# LEDSubMatrixHighDensity_v3.net
KiCad netlist of a schematic drawn in EAGLE
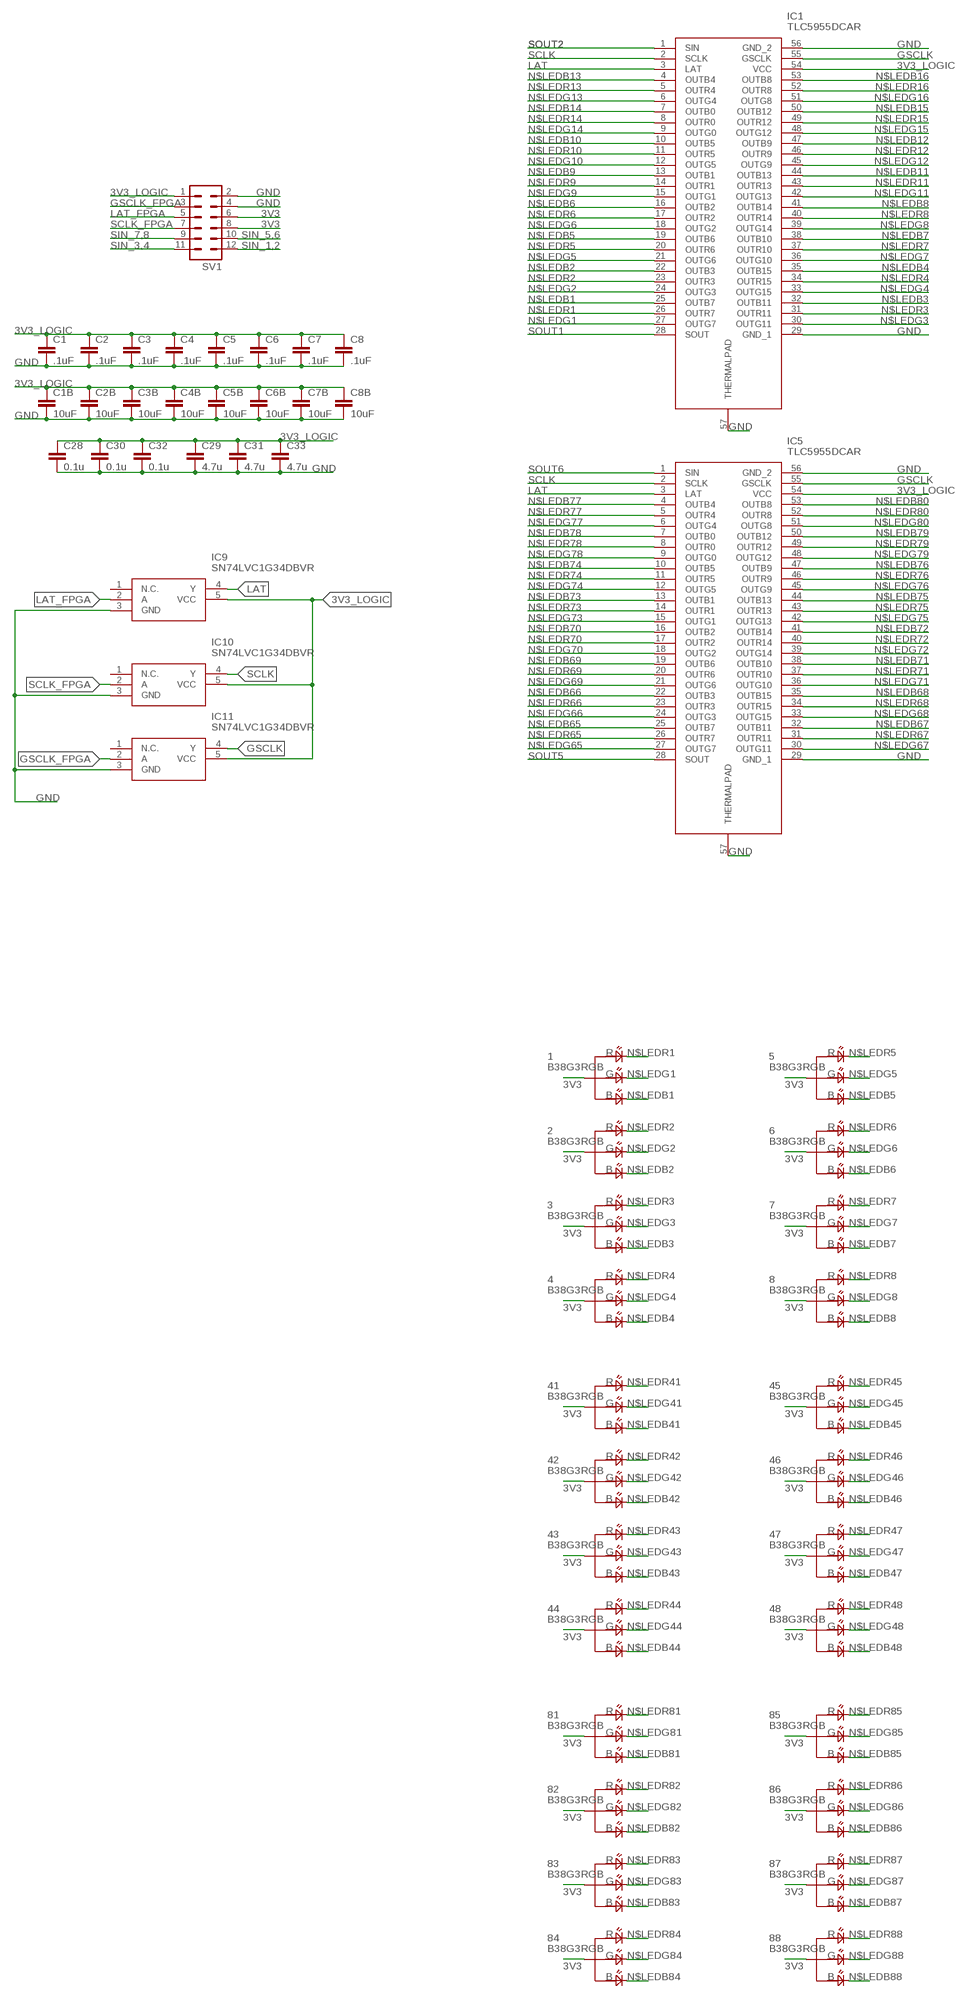
[diagram p0: schematic, sheet 1, part 1 of 2]
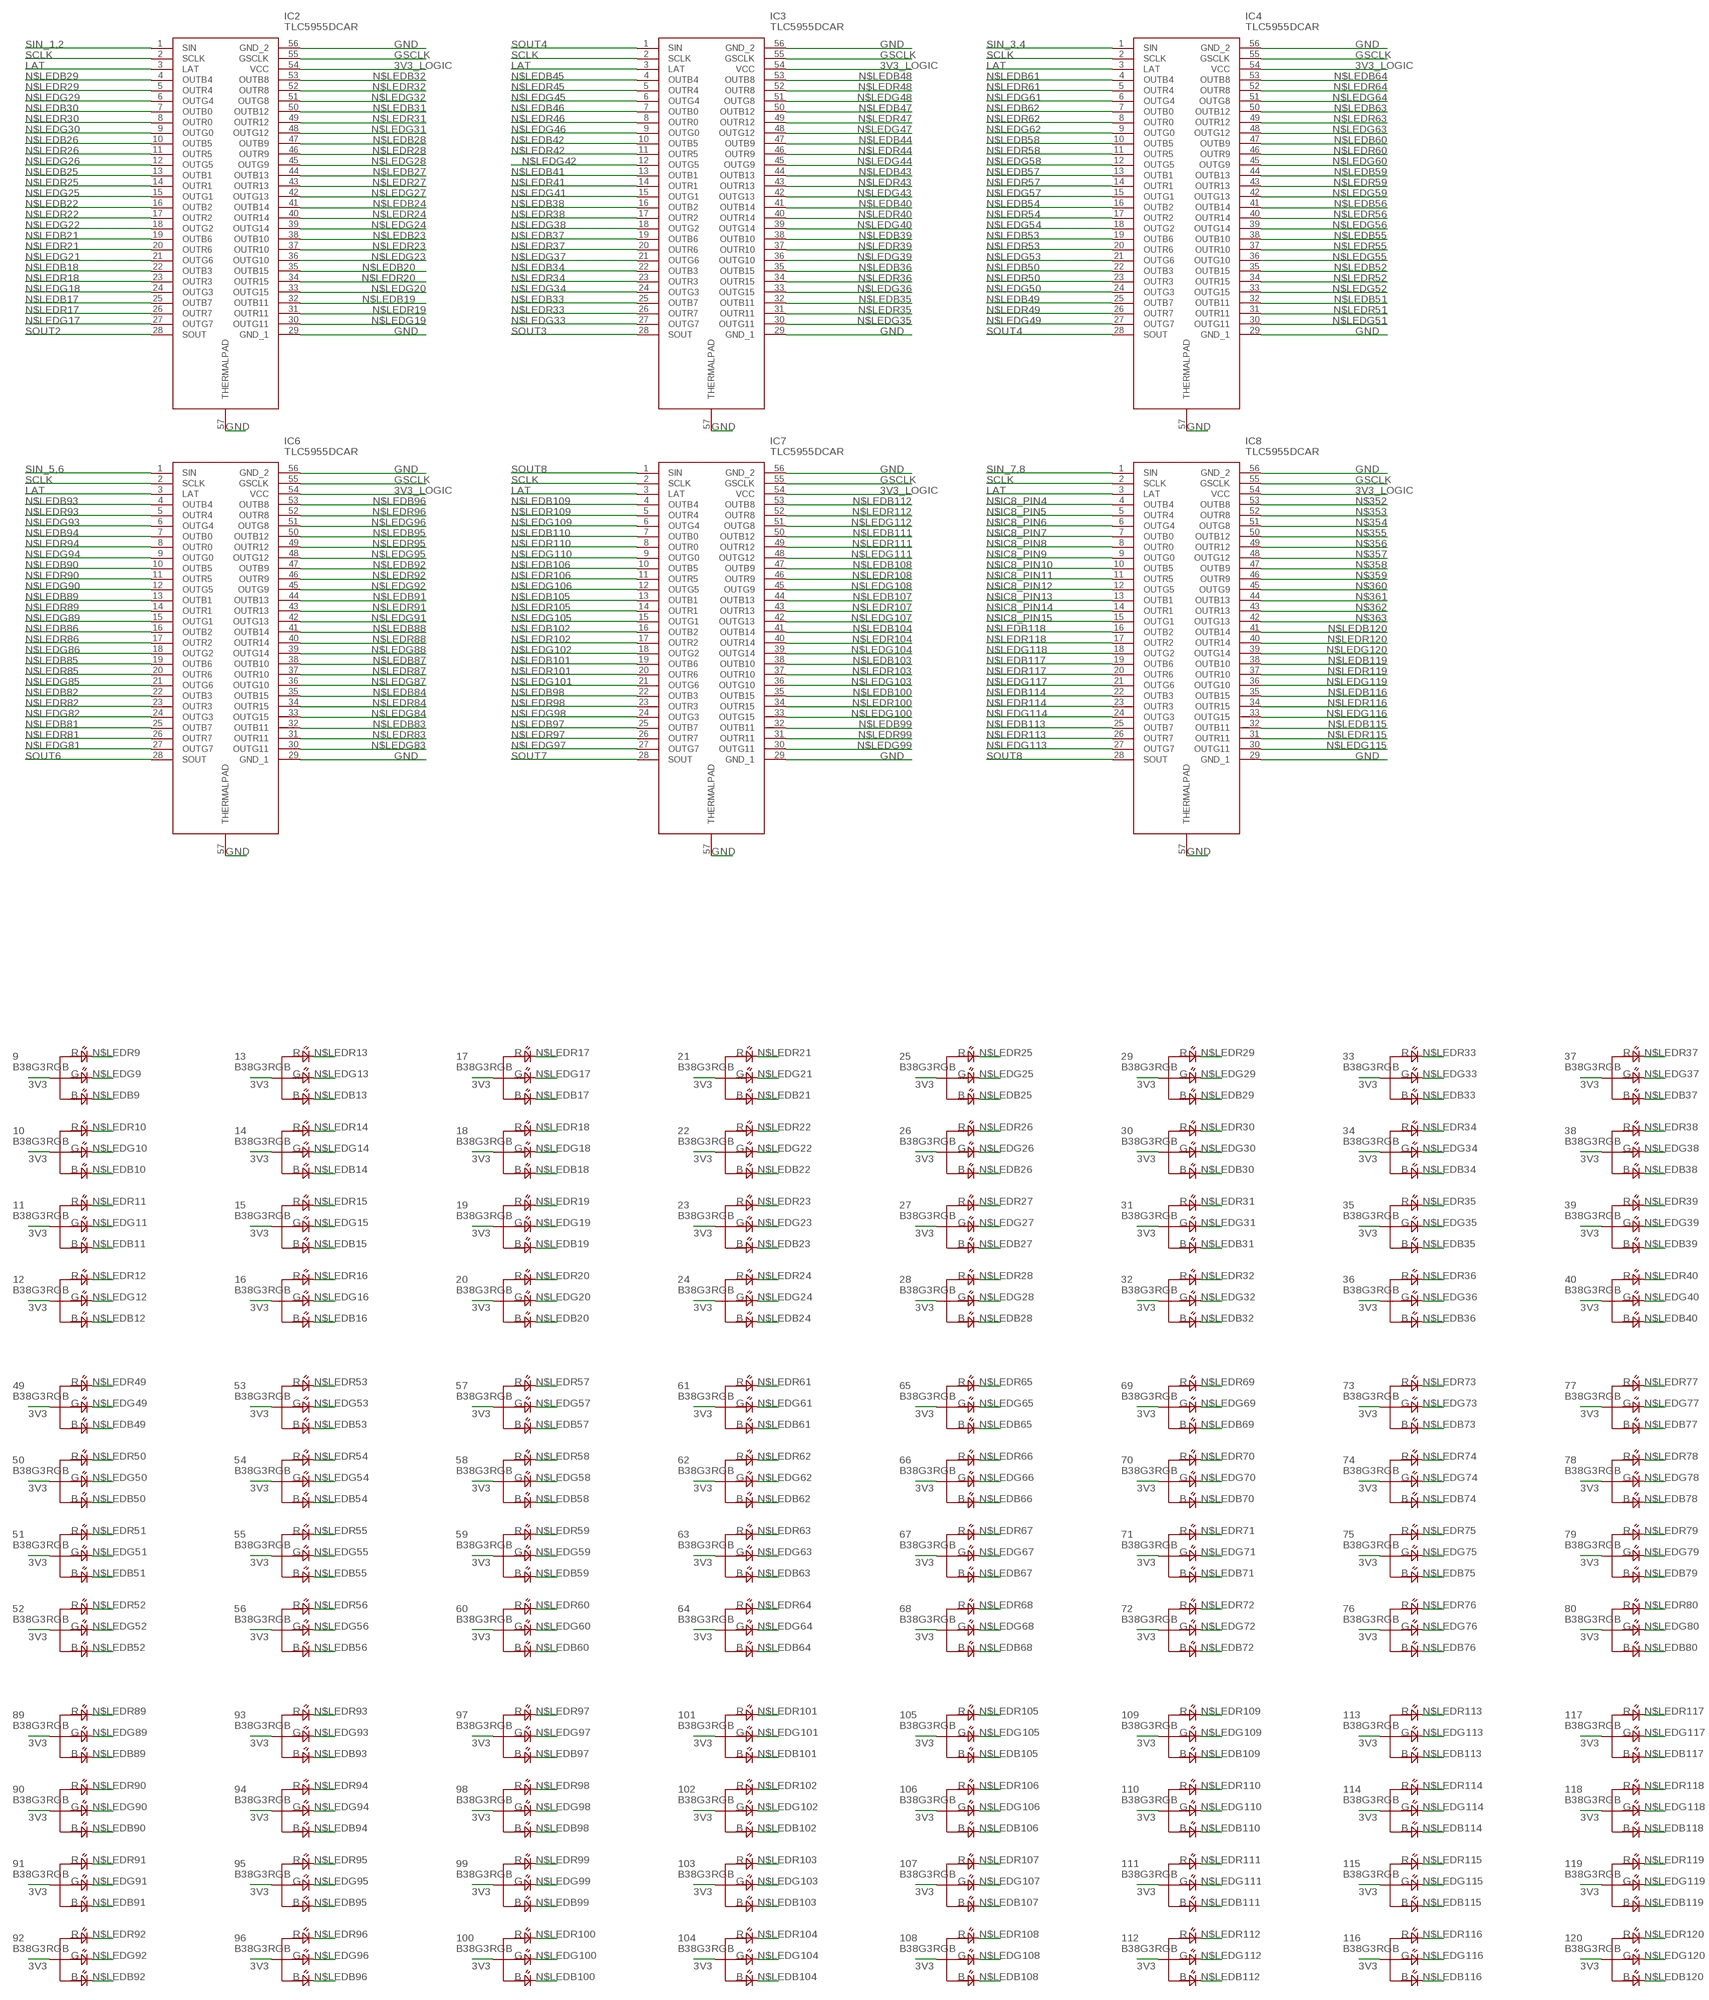
[diagram p1: schematic, sheet 1, part 2 of 2]

(export (version "E")
  (design (tool "Eeschema 10.0.6"))
  (components
    (comp (ref "1")
      (value "B38G3RGB")
      (footprint "eagle-import:B38G3RGB")
      (fields
        (field (name "ARROW_PART_NUMBER") "SML-LX0606IGC-TR")
        (field (name "MOUSER_PART_NUMBER") "696-SML-0606IGCTR")
      )
      (libsource (lib "eagle-import") (part "B38G3RGB"))
    )
    (comp (ref "2")
      (value "B38G3RGB")
      (footprint "eagle-import:B38G3RGB")
      (fields
        (field (name "ARROW_PART_NUMBER") "SML-LX0606IGC-TR")
        (field (name "MOUSER_PART_NUMBER") "696-SML-0606IGCTR")
      )
      (libsource (lib "eagle-import") (part "B38G3RGB"))
    )
    (comp (ref "3")
      (value "B38G3RGB")
      (footprint "eagle-import:B38G3RGB")
      (fields
        (field (name "ARROW_PART_NUMBER") "SML-LX0606IGC-TR")
        (field (name "MOUSER_PART_NUMBER") "696-SML-0606IGCTR")
      )
      (libsource (lib "eagle-import") (part "B38G3RGB"))
    )
    (comp (ref "4")
      (value "B38G3RGB")
      (footprint "eagle-import:B38G3RGB")
      (fields
        (field (name "ARROW_PART_NUMBER") "SML-LX0606IGC-TR")
        (field (name "MOUSER_PART_NUMBER") "696-SML-0606IGCTR")
      )
      (libsource (lib "eagle-import") (part "B38G3RGB"))
    )
    (comp (ref "5")
      (value "B38G3RGB")
      (footprint "eagle-import:B38G3RGB")
      (fields
        (field (name "ARROW_PART_NUMBER") "SML-LX0606IGC-TR")
        (field (name "MOUSER_PART_NUMBER") "696-SML-0606IGCTR")
      )
      (libsource (lib "eagle-import") (part "B38G3RGB"))
    )
    (comp (ref "6")
      (value "B38G3RGB")
      (footprint "eagle-import:B38G3RGB")
      (fields
        (field (name "ARROW_PART_NUMBER") "SML-LX0606IGC-TR")
        (field (name "MOUSER_PART_NUMBER") "696-SML-0606IGCTR")
      )
      (libsource (lib "eagle-import") (part "B38G3RGB"))
    )
    (comp (ref "7")
      (value "B38G3RGB")
      (footprint "eagle-import:B38G3RGB")
      (fields
        (field (name "ARROW_PART_NUMBER") "SML-LX0606IGC-TR")
        (field (name "MOUSER_PART_NUMBER") "696-SML-0606IGCTR")
      )
      (libsource (lib "eagle-import") (part "B38G3RGB"))
    )
    (comp (ref "8")
      (value "B38G3RGB")
      (footprint "eagle-import:B38G3RGB")
      (fields
        (field (name "ARROW_PART_NUMBER") "SML-LX0606IGC-TR")
        (field (name "MOUSER_PART_NUMBER") "696-SML-0606IGCTR")
      )
      (libsource (lib "eagle-import") (part "B38G3RGB"))
    )
    (comp (ref "9")
      (value "B38G3RGB")
      (footprint "eagle-import:B38G3RGB")
      (fields
        (field (name "ARROW_PART_NUMBER") "SML-LX0606IGC-TR")
        (field (name "MOUSER_PART_NUMBER") "696-SML-0606IGCTR")
      )
      (libsource (lib "eagle-import") (part "B38G3RGB"))
    )
    (comp (ref "10")
      (value "B38G3RGB")
      (footprint "eagle-import:B38G3RGB")
      (fields
        (field (name "ARROW_PART_NUMBER") "SML-LX0606IGC-TR")
        (field (name "MOUSER_PART_NUMBER") "696-SML-0606IGCTR")
      )
      (libsource (lib "eagle-import") (part "B38G3RGB"))
    )
    (comp (ref "11")
      (value "B38G3RGB")
      (footprint "eagle-import:B38G3RGB")
      (fields
        (field (name "ARROW_PART_NUMBER") "SML-LX0606IGC-TR")
        (field (name "MOUSER_PART_NUMBER") "696-SML-0606IGCTR")
      )
      (libsource (lib "eagle-import") (part "B38G3RGB"))
    )
    (comp (ref "12")
      (value "B38G3RGB")
      (footprint "eagle-import:B38G3RGB")
      (fields
        (field (name "ARROW_PART_NUMBER") "SML-LX0606IGC-TR")
        (field (name "MOUSER_PART_NUMBER") "696-SML-0606IGCTR")
      )
      (libsource (lib "eagle-import") (part "B38G3RGB"))
    )
    (comp (ref "13")
      (value "B38G3RGB")
      (footprint "eagle-import:B38G3RGB")
      (fields
        (field (name "ARROW_PART_NUMBER") "SML-LX0606IGC-TR")
        (field (name "MOUSER_PART_NUMBER") "696-SML-0606IGCTR")
      )
      (libsource (lib "eagle-import") (part "B38G3RGB"))
    )
    (comp (ref "14")
      (value "B38G3RGB")
      (footprint "eagle-import:B38G3RGB")
      (fields
        (field (name "ARROW_PART_NUMBER") "SML-LX0606IGC-TR")
        (field (name "MOUSER_PART_NUMBER") "696-SML-0606IGCTR")
      )
      (libsource (lib "eagle-import") (part "B38G3RGB"))
    )
    (comp (ref "15")
      (value "B38G3RGB")
      (footprint "eagle-import:B38G3RGB")
      (fields
        (field (name "ARROW_PART_NUMBER") "SML-LX0606IGC-TR")
        (field (name "MOUSER_PART_NUMBER") "696-SML-0606IGCTR")
      )
      (libsource (lib "eagle-import") (part "B38G3RGB"))
    )
    (comp (ref "16")
      (value "B38G3RGB")
      (footprint "eagle-import:B38G3RGB")
      (fields
        (field (name "ARROW_PART_NUMBER") "SML-LX0606IGC-TR")
        (field (name "MOUSER_PART_NUMBER") "696-SML-0606IGCTR")
      )
      (libsource (lib "eagle-import") (part "B38G3RGB"))
    )
    (comp (ref "17")
      (value "B38G3RGB")
      (footprint "eagle-import:B38G3RGB")
      (fields
        (field (name "ARROW_PART_NUMBER") "SML-LX0606IGC-TR")
        (field (name "MOUSER_PART_NUMBER") "696-SML-0606IGCTR")
      )
      (libsource (lib "eagle-import") (part "B38G3RGB"))
    )
    (comp (ref "18")
      (value "B38G3RGB")
      (footprint "eagle-import:B38G3RGB")
      (fields
        (field (name "ARROW_PART_NUMBER") "SML-LX0606IGC-TR")
        (field (name "MOUSER_PART_NUMBER") "696-SML-0606IGCTR")
      )
      (libsource (lib "eagle-import") (part "B38G3RGB"))
    )
    (comp (ref "19")
      (value "B38G3RGB")
      (footprint "eagle-import:B38G3RGB")
      (fields
        (field (name "ARROW_PART_NUMBER") "SML-LX0606IGC-TR")
        (field (name "MOUSER_PART_NUMBER") "696-SML-0606IGCTR")
      )
      (libsource (lib "eagle-import") (part "B38G3RGB"))
    )
    (comp (ref "20")
      (value "B38G3RGB")
      (footprint "eagle-import:B38G3RGB")
      (fields
        (field (name "ARROW_PART_NUMBER") "SML-LX0606IGC-TR")
        (field (name "MOUSER_PART_NUMBER") "696-SML-0606IGCTR")
      )
      (libsource (lib "eagle-import") (part "B38G3RGB"))
    )
    (comp (ref "21")
      (value "B38G3RGB")
      (footprint "eagle-import:B38G3RGB")
      (fields
        (field (name "ARROW_PART_NUMBER") "SML-LX0606IGC-TR")
        (field (name "MOUSER_PART_NUMBER") "696-SML-0606IGCTR")
      )
      (libsource (lib "eagle-import") (part "B38G3RGB"))
    )
    (comp (ref "22")
      (value "B38G3RGB")
      (footprint "eagle-import:B38G3RGB")
      (fields
        (field (name "ARROW_PART_NUMBER") "SML-LX0606IGC-TR")
        (field (name "MOUSER_PART_NUMBER") "696-SML-0606IGCTR")
      )
      (libsource (lib "eagle-import") (part "B38G3RGB"))
    )
    (comp (ref "23")
      (value "B38G3RGB")
      (footprint "eagle-import:B38G3RGB")
      (fields
        (field (name "ARROW_PART_NUMBER") "SML-LX0606IGC-TR")
        (field (name "MOUSER_PART_NUMBER") "696-SML-0606IGCTR")
      )
      (libsource (lib "eagle-import") (part "B38G3RGB"))
    )
    (comp (ref "24")
      (value "B38G3RGB")
      (footprint "eagle-import:B38G3RGB")
      (fields
        (field (name "ARROW_PART_NUMBER") "SML-LX0606IGC-TR")
        (field (name "MOUSER_PART_NUMBER") "696-SML-0606IGCTR")
      )
      (libsource (lib "eagle-import") (part "B38G3RGB"))
    )
    (comp (ref "25")
      (value "B38G3RGB")
      (footprint "eagle-import:B38G3RGB")
      (fields
        (field (name "ARROW_PART_NUMBER") "SML-LX0606IGC-TR")
        (field (name "MOUSER_PART_NUMBER") "696-SML-0606IGCTR")
      )
      (libsource (lib "eagle-import") (part "B38G3RGB"))
    )
    (comp (ref "26")
      (value "B38G3RGB")
      (footprint "eagle-import:B38G3RGB")
      (fields
        (field (name "ARROW_PART_NUMBER") "SML-LX0606IGC-TR")
        (field (name "MOUSER_PART_NUMBER") "696-SML-0606IGCTR")
      )
      (libsource (lib "eagle-import") (part "B38G3RGB"))
    )
    (comp (ref "27")
      (value "B38G3RGB")
      (footprint "eagle-import:B38G3RGB")
      (fields
        (field (name "ARROW_PART_NUMBER") "SML-LX0606IGC-TR")
        (field (name "MOUSER_PART_NUMBER") "696-SML-0606IGCTR")
      )
      (libsource (lib "eagle-import") (part "B38G3RGB"))
    )
    (comp (ref "28")
      (value "B38G3RGB")
      (footprint "eagle-import:B38G3RGB")
      (fields
        (field (name "ARROW_PART_NUMBER") "SML-LX0606IGC-TR")
        (field (name "MOUSER_PART_NUMBER") "696-SML-0606IGCTR")
      )
      (libsource (lib "eagle-import") (part "B38G3RGB"))
    )
    (comp (ref "29")
      (value "B38G3RGB")
      (footprint "eagle-import:B38G3RGB")
      (fields
        (field (name "ARROW_PART_NUMBER") "SML-LX0606IGC-TR")
        (field (name "MOUSER_PART_NUMBER") "696-SML-0606IGCTR")
      )
      (libsource (lib "eagle-import") (part "B38G3RGB"))
    )
    (comp (ref "30")
      (value "B38G3RGB")
      (footprint "eagle-import:B38G3RGB")
      (fields
        (field (name "ARROW_PART_NUMBER") "SML-LX0606IGC-TR")
        (field (name "MOUSER_PART_NUMBER") "696-SML-0606IGCTR")
      )
      (libsource (lib "eagle-import") (part "B38G3RGB"))
    )
    (comp (ref "31")
      (value "B38G3RGB")
      (footprint "eagle-import:B38G3RGB")
      (fields
        (field (name "ARROW_PART_NUMBER") "SML-LX0606IGC-TR")
        (field (name "MOUSER_PART_NUMBER") "696-SML-0606IGCTR")
      )
      (libsource (lib "eagle-import") (part "B38G3RGB"))
    )
    (comp (ref "32")
      (value "B38G3RGB")
      (footprint "eagle-import:B38G3RGB")
      (fields
        (field (name "ARROW_PART_NUMBER") "SML-LX0606IGC-TR")
        (field (name "MOUSER_PART_NUMBER") "696-SML-0606IGCTR")
      )
      (libsource (lib "eagle-import") (part "B38G3RGB"))
    )
    (comp (ref "33")
      (value "B38G3RGB")
      (footprint "eagle-import:B38G3RGB")
      (fields
        (field (name "ARROW_PART_NUMBER") "SML-LX0606IGC-TR")
        (field (name "MOUSER_PART_NUMBER") "696-SML-0606IGCTR")
      )
      (libsource (lib "eagle-import") (part "B38G3RGB"))
    )
    (comp (ref "34")
      (value "B38G3RGB")
      (footprint "eagle-import:B38G3RGB")
      (fields
        (field (name "ARROW_PART_NUMBER") "SML-LX0606IGC-TR")
        (field (name "MOUSER_PART_NUMBER") "696-SML-0606IGCTR")
      )
      (libsource (lib "eagle-import") (part "B38G3RGB"))
    )
    (comp (ref "35")
      (value "B38G3RGB")
      (footprint "eagle-import:B38G3RGB")
      (fields
        (field (name "ARROW_PART_NUMBER") "SML-LX0606IGC-TR")
        (field (name "MOUSER_PART_NUMBER") "696-SML-0606IGCTR")
      )
      (libsource (lib "eagle-import") (part "B38G3RGB"))
    )
    (comp (ref "36")
      (value "B38G3RGB")
      (footprint "eagle-import:B38G3RGB")
      (fields
        (field (name "ARROW_PART_NUMBER") "SML-LX0606IGC-TR")
        (field (name "MOUSER_PART_NUMBER") "696-SML-0606IGCTR")
      )
      (libsource (lib "eagle-import") (part "B38G3RGB"))
    )
    (comp (ref "37")
      (value "B38G3RGB")
      (footprint "eagle-import:B38G3RGB")
      (fields
        (field (name "ARROW_PART_NUMBER") "SML-LX0606IGC-TR")
        (field (name "MOUSER_PART_NUMBER") "696-SML-0606IGCTR")
      )
      (libsource (lib "eagle-import") (part "B38G3RGB"))
    )
    (comp (ref "38")
      (value "B38G3RGB")
      (footprint "eagle-import:B38G3RGB")
      (fields
        (field (name "ARROW_PART_NUMBER") "SML-LX0606IGC-TR")
        (field (name "MOUSER_PART_NUMBER") "696-SML-0606IGCTR")
      )
      (libsource (lib "eagle-import") (part "B38G3RGB"))
    )
    (comp (ref "39")
      (value "B38G3RGB")
      (footprint "eagle-import:B38G3RGB")
      (fields
        (field (name "ARROW_PART_NUMBER") "SML-LX0606IGC-TR")
        (field (name "MOUSER_PART_NUMBER") "696-SML-0606IGCTR")
      )
      (libsource (lib "eagle-import") (part "B38G3RGB"))
    )
    (comp (ref "40")
      (value "B38G3RGB")
      (footprint "eagle-import:B38G3RGB")
      (fields
        (field (name "ARROW_PART_NUMBER") "SML-LX0606IGC-TR")
        (field (name "MOUSER_PART_NUMBER") "696-SML-0606IGCTR")
      )
      (libsource (lib "eagle-import") (part "B38G3RGB"))
    )
    (comp (ref "41")
      (value "B38G3RGB")
      (footprint "eagle-import:B38G3RGB")
      (fields
        (field (name "ARROW_PART_NUMBER") "SML-LX0606IGC-TR")
        (field (name "MOUSER_PART_NUMBER") "696-SML-0606IGCTR")
      )
      (libsource (lib "eagle-import") (part "B38G3RGB"))
    )
    (comp (ref "42")
      (value "B38G3RGB")
      (footprint "eagle-import:B38G3RGB")
      (fields
        (field (name "ARROW_PART_NUMBER") "SML-LX0606IGC-TR")
        (field (name "MOUSER_PART_NUMBER") "696-SML-0606IGCTR")
      )
      (libsource (lib "eagle-import") (part "B38G3RGB"))
    )
    (comp (ref "43")
      (value "B38G3RGB")
      (footprint "eagle-import:B38G3RGB")
      (fields
        (field (name "ARROW_PART_NUMBER") "SML-LX0606IGC-TR")
        (field (name "MOUSER_PART_NUMBER") "696-SML-0606IGCTR")
      )
      (libsource (lib "eagle-import") (part "B38G3RGB"))
    )
    (comp (ref "44")
      (value "B38G3RGB")
      (footprint "eagle-import:B38G3RGB")
      (fields
        (field (name "ARROW_PART_NUMBER") "SML-LX0606IGC-TR")
        (field (name "MOUSER_PART_NUMBER") "696-SML-0606IGCTR")
      )
      (libsource (lib "eagle-import") (part "B38G3RGB"))
    )
    (comp (ref "45")
      (value "B38G3RGB")
      (footprint "eagle-import:B38G3RGB")
      (fields
        (field (name "ARROW_PART_NUMBER") "SML-LX0606IGC-TR")
        (field (name "MOUSER_PART_NUMBER") "696-SML-0606IGCTR")
      )
      (libsource (lib "eagle-import") (part "B38G3RGB"))
    )
    (comp (ref "46")
      (value "B38G3RGB")
      (footprint "eagle-import:B38G3RGB")
      (fields
        (field (name "ARROW_PART_NUMBER") "SML-LX0606IGC-TR")
        (field (name "MOUSER_PART_NUMBER") "696-SML-0606IGCTR")
      )
      (libsource (lib "eagle-import") (part "B38G3RGB"))
    )
    (comp (ref "47")
      (value "B38G3RGB")
      (footprint "eagle-import:B38G3RGB")
      (fields
        (field (name "ARROW_PART_NUMBER") "SML-LX0606IGC-TR")
        (field (name "MOUSER_PART_NUMBER") "696-SML-0606IGCTR")
      )
      (libsource (lib "eagle-import") (part "B38G3RGB"))
    )
    (comp (ref "48")
      (value "B38G3RGB")
      (footprint "eagle-import:B38G3RGB")
      (fields
        (field (name "ARROW_PART_NUMBER") "SML-LX0606IGC-TR")
        (field (name "MOUSER_PART_NUMBER") "696-SML-0606IGCTR")
      )
      (libsource (lib "eagle-import") (part "B38G3RGB"))
    )
    (comp (ref "49")
      (value "B38G3RGB")
      (footprint "eagle-import:B38G3RGB")
      (fields
        (field (name "ARROW_PART_NUMBER") "SML-LX0606IGC-TR")
        (field (name "MOUSER_PART_NUMBER") "696-SML-0606IGCTR")
      )
      (libsource (lib "eagle-import") (part "B38G3RGB"))
    )
    (comp (ref "50")
      (value "B38G3RGB")
      (footprint "eagle-import:B38G3RGB")
      (fields
        (field (name "ARROW_PART_NUMBER") "SML-LX0606IGC-TR")
        (field (name "MOUSER_PART_NUMBER") "696-SML-0606IGCTR")
      )
      (libsource (lib "eagle-import") (part "B38G3RGB"))
    )
    (comp (ref "51")
      (value "B38G3RGB")
      (footprint "eagle-import:B38G3RGB")
      (fields
        (field (name "ARROW_PART_NUMBER") "SML-LX0606IGC-TR")
        (field (name "MOUSER_PART_NUMBER") "696-SML-0606IGCTR")
      )
      (libsource (lib "eagle-import") (part "B38G3RGB"))
    )
    (comp (ref "52")
      (value "B38G3RGB")
      (footprint "eagle-import:B38G3RGB")
      (fields
        (field (name "ARROW_PART_NUMBER") "SML-LX0606IGC-TR")
        (field (name "MOUSER_PART_NUMBER") "696-SML-0606IGCTR")
      )
      (libsource (lib "eagle-import") (part "B38G3RGB"))
    )
    (comp (ref "53")
      (value "B38G3RGB")
      (footprint "eagle-import:B38G3RGB")
      (fields
        (field (name "ARROW_PART_NUMBER") "SML-LX0606IGC-TR")
        (field (name "MOUSER_PART_NUMBER") "696-SML-0606IGCTR")
      )
      (libsource (lib "eagle-import") (part "B38G3RGB"))
    )
    (comp (ref "54")
      (value "B38G3RGB")
      (footprint "eagle-import:B38G3RGB")
      (fields
        (field (name "ARROW_PART_NUMBER") "SML-LX0606IGC-TR")
        (field (name "MOUSER_PART_NUMBER") "696-SML-0606IGCTR")
      )
      (libsource (lib "eagle-import") (part "B38G3RGB"))
    )
    (comp (ref "55")
      (value "B38G3RGB")
      (footprint "eagle-import:B38G3RGB")
      (fields
        (field (name "ARROW_PART_NUMBER") "SML-LX0606IGC-TR")
        (field (name "MOUSER_PART_NUMBER") "696-SML-0606IGCTR")
      )
      (libsource (lib "eagle-import") (part "B38G3RGB"))
    )
    (comp (ref "56")
      (value "B38G3RGB")
      (footprint "eagle-import:B38G3RGB")
      (fields
        (field (name "ARROW_PART_NUMBER") "SML-LX0606IGC-TR")
        (field (name "MOUSER_PART_NUMBER") "696-SML-0606IGCTR")
      )
      (libsource (lib "eagle-import") (part "B38G3RGB"))
    )
    (comp (ref "57")
      (value "B38G3RGB")
      (footprint "eagle-import:B38G3RGB")
      (fields
        (field (name "ARROW_PART_NUMBER") "SML-LX0606IGC-TR")
        (field (name "MOUSER_PART_NUMBER") "696-SML-0606IGCTR")
      )
      (libsource (lib "eagle-import") (part "B38G3RGB"))
    )
    (comp (ref "58")
      (value "B38G3RGB")
      (footprint "eagle-import:B38G3RGB")
      (fields
        (field (name "ARROW_PART_NUMBER") "SML-LX0606IGC-TR")
        (field (name "MOUSER_PART_NUMBER") "696-SML-0606IGCTR")
      )
      (libsource (lib "eagle-import") (part "B38G3RGB"))
    )
    (comp (ref "59")
      (value "B38G3RGB")
      (footprint "eagle-import:B38G3RGB")
      (fields
        (field (name "ARROW_PART_NUMBER") "SML-LX0606IGC-TR")
        (field (name "MOUSER_PART_NUMBER") "696-SML-0606IGCTR")
      )
      (libsource (lib "eagle-import") (part "B38G3RGB"))
    )
    (comp (ref "60")
      (value "B38G3RGB")
      (footprint "eagle-import:B38G3RGB")
      (fields
        (field (name "ARROW_PART_NUMBER") "SML-LX0606IGC-TR")
        (field (name "MOUSER_PART_NUMBER") "696-SML-0606IGCTR")
      )
      (libsource (lib "eagle-import") (part "B38G3RGB"))
    )
    (comp (ref "61")
      (value "B38G3RGB")
      (footprint "eagle-import:B38G3RGB")
      (fields
        (field (name "ARROW_PART_NUMBER") "SML-LX0606IGC-TR")
        (field (name "MOUSER_PART_NUMBER") "696-SML-0606IGCTR")
      )
      (libsource (lib "eagle-import") (part "B38G3RGB"))
    )
    (comp (ref "62")
      (value "B38G3RGB")
      (footprint "eagle-import:B38G3RGB")
      (fields
        (field (name "ARROW_PART_NUMBER") "SML-LX0606IGC-TR")
        (field (name "MOUSER_PART_NUMBER") "696-SML-0606IGCTR")
      )
      (libsource (lib "eagle-import") (part "B38G3RGB"))
    )
    (comp (ref "63")
      (value "B38G3RGB")
      (footprint "eagle-import:B38G3RGB")
      (fields
        (field (name "ARROW_PART_NUMBER") "SML-LX0606IGC-TR")
        (field (name "MOUSER_PART_NUMBER") "696-SML-0606IGCTR")
      )
      (libsource (lib "eagle-import") (part "B38G3RGB"))
    )
    (comp (ref "64")
      (value "B38G3RGB")
      (footprint "eagle-import:B38G3RGB")
      (fields
        (field (name "ARROW_PART_NUMBER") "SML-LX0606IGC-TR")
        (field (name "MOUSER_PART_NUMBER") "696-SML-0606IGCTR")
      )
      (libsource (lib "eagle-import") (part "B38G3RGB"))
    )
    (comp (ref "65")
      (value "B38G3RGB")
      (footprint "eagle-import:B38G3RGB")
      (fields
        (field (name "ARROW_PART_NUMBER") "SML-LX0606IGC-TR")
        (field (name "MOUSER_PART_NUMBER") "696-SML-0606IGCTR")
      )
      (libsource (lib "eagle-import") (part "B38G3RGB"))
    )
    (comp (ref "66")
      (value "B38G3RGB")
      (footprint "eagle-import:B38G3RGB")
      (fields
        (field (name "ARROW_PART_NUMBER") "SML-LX0606IGC-TR")
        (field (name "MOUSER_PART_NUMBER") "696-SML-0606IGCTR")
      )
      (libsource (lib "eagle-import") (part "B38G3RGB"))
    )
    (comp (ref "67")
      (value "B38G3RGB")
      (footprint "eagle-import:B38G3RGB")
      (fields
        (field (name "ARROW_PART_NUMBER") "SML-LX0606IGC-TR")
        (field (name "MOUSER_PART_NUMBER") "696-SML-0606IGCTR")
      )
      (libsource (lib "eagle-import") (part "B38G3RGB"))
    )
    (comp (ref "68")
      (value "B38G3RGB")
      (footprint "eagle-import:B38G3RGB")
      (fields
        (field (name "ARROW_PART_NUMBER") "SML-LX0606IGC-TR")
        (field (name "MOUSER_PART_NUMBER") "696-SML-0606IGCTR")
      )
      (libsource (lib "eagle-import") (part "B38G3RGB"))
    )
    (comp (ref "69")
      (value "B38G3RGB")
      (footprint "eagle-import:B38G3RGB")
      (fields
        (field (name "ARROW_PART_NUMBER") "SML-LX0606IGC-TR")
        (field (name "MOUSER_PART_NUMBER") "696-SML-0606IGCTR")
      )
      (libsource (lib "eagle-import") (part "B38G3RGB"))
    )
    (comp (ref "70")
      (value "B38G3RGB")
      (footprint "eagle-import:B38G3RGB")
      (fields
        (field (name "ARROW_PART_NUMBER") "SML-LX0606IGC-TR")
        (field (name "MOUSER_PART_NUMBER") "696-SML-0606IGCTR")
      )
      (libsource (lib "eagle-import") (part "B38G3RGB"))
    )
    (comp (ref "71")
      (value "B38G3RGB")
      (footprint "eagle-import:B38G3RGB")
      (fields
        (field (name "ARROW_PART_NUMBER") "SML-LX0606IGC-TR")
        (field (name "MOUSER_PART_NUMBER") "696-SML-0606IGCTR")
      )
      (libsource (lib "eagle-import") (part "B38G3RGB"))
    )
    (comp (ref "72")
      (value "B38G3RGB")
      (footprint "eagle-import:B38G3RGB")
      (fields
        (field (name "ARROW_PART_NUMBER") "SML-LX0606IGC-TR")
        (field (name "MOUSER_PART_NUMBER") "696-SML-0606IGCTR")
      )
      (libsource (lib "eagle-import") (part "B38G3RGB"))
    )
    (comp (ref "73")
      (value "B38G3RGB")
      (footprint "eagle-import:B38G3RGB")
      (fields
        (field (name "ARROW_PART_NUMBER") "SML-LX0606IGC-TR")
        (field (name "MOUSER_PART_NUMBER") "696-SML-0606IGCTR")
      )
      (libsource (lib "eagle-import") (part "B38G3RGB"))
    )
    (comp (ref "74")
      (value "B38G3RGB")
      (footprint "eagle-import:B38G3RGB")
      (fields
        (field (name "ARROW_PART_NUMBER") "SML-LX0606IGC-TR")
        (field (name "MOUSER_PART_NUMBER") "696-SML-0606IGCTR")
      )
      (libsource (lib "eagle-import") (part "B38G3RGB"))
    )
    (comp (ref "75")
      (value "B38G3RGB")
      (footprint "eagle-import:B38G3RGB")
      (fields
        (field (name "ARROW_PART_NUMBER") "SML-LX0606IGC-TR")
        (field (name "MOUSER_PART_NUMBER") "696-SML-0606IGCTR")
      )
      (libsource (lib "eagle-import") (part "B38G3RGB"))
    )
    (comp (ref "76")
      (value "B38G3RGB")
      (footprint "eagle-import:B38G3RGB")
      (fields
        (field (name "ARROW_PART_NUMBER") "SML-LX0606IGC-TR")
        (field (name "MOUSER_PART_NUMBER") "696-SML-0606IGCTR")
      )
      (libsource (lib "eagle-import") (part "B38G3RGB"))
    )
    (comp (ref "77")
      (value "B38G3RGB")
      (footprint "eagle-import:B38G3RGB")
      (fields
        (field (name "ARROW_PART_NUMBER") "SML-LX0606IGC-TR")
        (field (name "MOUSER_PART_NUMBER") "696-SML-0606IGCTR")
      )
      (libsource (lib "eagle-import") (part "B38G3RGB"))
    )
    (comp (ref "78")
      (value "B38G3RGB")
      (footprint "eagle-import:B38G3RGB")
      (fields
        (field (name "ARROW_PART_NUMBER") "SML-LX0606IGC-TR")
        (field (name "MOUSER_PART_NUMBER") "696-SML-0606IGCTR")
      )
      (libsource (lib "eagle-import") (part "B38G3RGB"))
    )
    (comp (ref "79")
      (value "B38G3RGB")
      (footprint "eagle-import:B38G3RGB")
      (fields
        (field (name "ARROW_PART_NUMBER") "SML-LX0606IGC-TR")
        (field (name "MOUSER_PART_NUMBER") "696-SML-0606IGCTR")
      )
      (libsource (lib "eagle-import") (part "B38G3RGB"))
    )
    (comp (ref "80")
      (value "B38G3RGB")
      (footprint "eagle-import:B38G3RGB")
      (fields
        (field (name "ARROW_PART_NUMBER") "SML-LX0606IGC-TR")
        (field (name "MOUSER_PART_NUMBER") "696-SML-0606IGCTR")
      )
      (libsource (lib "eagle-import") (part "B38G3RGB"))
    )
    (comp (ref "81")
      (value "B38G3RGB")
      (footprint "eagle-import:B38G3RGB")
      (fields
        (field (name "ARROW_PART_NUMBER") "SML-LX0606IGC-TR")
        (field (name "MOUSER_PART_NUMBER") "696-SML-0606IGCTR")
      )
      (libsource (lib "eagle-import") (part "B38G3RGB"))
    )
    (comp (ref "82")
      (value "B38G3RGB")
      (footprint "eagle-import:B38G3RGB")
      (fields
        (field (name "ARROW_PART_NUMBER") "SML-LX0606IGC-TR")
        (field (name "MOUSER_PART_NUMBER") "696-SML-0606IGCTR")
      )
      (libsource (lib "eagle-import") (part "B38G3RGB"))
    )
    (comp (ref "83")
      (value "B38G3RGB")
      (footprint "eagle-import:B38G3RGB")
      (fields
        (field (name "ARROW_PART_NUMBER") "SML-LX0606IGC-TR")
        (field (name "MOUSER_PART_NUMBER") "696-SML-0606IGCTR")
      )
      (libsource (lib "eagle-import") (part "B38G3RGB"))
    )
    (comp (ref "84")
      (value "B38G3RGB")
      (footprint "eagle-import:B38G3RGB")
      (fields
        (field (name "ARROW_PART_NUMBER") "SML-LX0606IGC-TR")
        (field (name "MOUSER_PART_NUMBER") "696-SML-0606IGCTR")
      )
      (libsource (lib "eagle-import") (part "B38G3RGB"))
    )
    (comp (ref "85")
      (value "B38G3RGB")
      (footprint "eagle-import:B38G3RGB")
      (fields
        (field (name "ARROW_PART_NUMBER") "SML-LX0606IGC-TR")
        (field (name "MOUSER_PART_NUMBER") "696-SML-0606IGCTR")
      )
      (libsource (lib "eagle-import") (part "B38G3RGB"))
    )
    (comp (ref "86")
      (value "B38G3RGB")
      (footprint "eagle-import:B38G3RGB")
      (fields
        (field (name "ARROW_PART_NUMBER") "SML-LX0606IGC-TR")
        (field (name "MOUSER_PART_NUMBER") "696-SML-0606IGCTR")
      )
      (libsource (lib "eagle-import") (part "B38G3RGB"))
    )
    (comp (ref "87")
      (value "B38G3RGB")
      (footprint "eagle-import:B38G3RGB")
      (fields
        (field (name "ARROW_PART_NUMBER") "SML-LX0606IGC-TR")
        (field (name "MOUSER_PART_NUMBER") "696-SML-0606IGCTR")
      )
      (libsource (lib "eagle-import") (part "B38G3RGB"))
    )
    (comp (ref "88")
      (value "B38G3RGB")
      (footprint "eagle-import:B38G3RGB")
      (fields
        (field (name "ARROW_PART_NUMBER") "SML-LX0606IGC-TR")
        (field (name "MOUSER_PART_NUMBER") "696-SML-0606IGCTR")
      )
      (libsource (lib "eagle-import") (part "B38G3RGB"))
    )
    (comp (ref "89")
      (value "B38G3RGB")
      (footprint "eagle-import:B38G3RGB")
      (fields
        (field (name "ARROW_PART_NUMBER") "SML-LX0606IGC-TR")
        (field (name "MOUSER_PART_NUMBER") "696-SML-0606IGCTR")
      )
      (libsource (lib "eagle-import") (part "B38G3RGB"))
    )
    (comp (ref "90")
      (value "B38G3RGB")
      (footprint "eagle-import:B38G3RGB")
      (fields
        (field (name "ARROW_PART_NUMBER") "SML-LX0606IGC-TR")
        (field (name "MOUSER_PART_NUMBER") "696-SML-0606IGCTR")
      )
      (libsource (lib "eagle-import") (part "B38G3RGB"))
    )
    (comp (ref "91")
      (value "B38G3RGB")
      (footprint "eagle-import:B38G3RGB")
      (fields
        (field (name "ARROW_PART_NUMBER") "SML-LX0606IGC-TR")
        (field (name "MOUSER_PART_NUMBER") "696-SML-0606IGCTR")
      )
      (libsource (lib "eagle-import") (part "B38G3RGB"))
    )
    (comp (ref "92")
      (value "B38G3RGB")
      (footprint "eagle-import:B38G3RGB")
      (fields
        (field (name "ARROW_PART_NUMBER") "SML-LX0606IGC-TR")
        (field (name "MOUSER_PART_NUMBER") "696-SML-0606IGCTR")
      )
      (libsource (lib "eagle-import") (part "B38G3RGB"))
    )
    (comp (ref "93")
      (value "B38G3RGB")
      (footprint "eagle-import:B38G3RGB")
      (fields
        (field (name "ARROW_PART_NUMBER") "SML-LX0606IGC-TR")
        (field (name "MOUSER_PART_NUMBER") "696-SML-0606IGCTR")
      )
      (libsource (lib "eagle-import") (part "B38G3RGB"))
    )
    (comp (ref "94")
      (value "B38G3RGB")
      (footprint "eagle-import:B38G3RGB")
      (fields
        (field (name "ARROW_PART_NUMBER") "SML-LX0606IGC-TR")
        (field (name "MOUSER_PART_NUMBER") "696-SML-0606IGCTR")
      )
      (libsource (lib "eagle-import") (part "B38G3RGB"))
    )
    (comp (ref "95")
      (value "B38G3RGB")
      (footprint "eagle-import:B38G3RGB")
      (fields
        (field (name "ARROW_PART_NUMBER") "SML-LX0606IGC-TR")
        (field (name "MOUSER_PART_NUMBER") "696-SML-0606IGCTR")
      )
      (libsource (lib "eagle-import") (part "B38G3RGB"))
    )
    (comp (ref "96")
      (value "B38G3RGB")
      (footprint "eagle-import:B38G3RGB")
      (fields
        (field (name "ARROW_PART_NUMBER") "SML-LX0606IGC-TR")
        (field (name "MOUSER_PART_NUMBER") "696-SML-0606IGCTR")
      )
      (libsource (lib "eagle-import") (part "B38G3RGB"))
    )
    (comp (ref "97")
      (value "B38G3RGB")
      (footprint "eagle-import:B38G3RGB")
      (fields
        (field (name "ARROW_PART_NUMBER") "SML-LX0606IGC-TR")
        (field (name "MOUSER_PART_NUMBER") "696-SML-0606IGCTR")
      )
      (libsource (lib "eagle-import") (part "B38G3RGB"))
    )
    (comp (ref "98")
      (value "B38G3RGB")
      (footprint "eagle-import:B38G3RGB")
      (fields
        (field (name "ARROW_PART_NUMBER") "SML-LX0606IGC-TR")
        (field (name "MOUSER_PART_NUMBER") "696-SML-0606IGCTR")
      )
      (libsource (lib "eagle-import") (part "B38G3RGB"))
    )
    (comp (ref "99")
      (value "B38G3RGB")
      (footprint "eagle-import:B38G3RGB")
      (fields
        (field (name "ARROW_PART_NUMBER") "SML-LX0606IGC-TR")
        (field (name "MOUSER_PART_NUMBER") "696-SML-0606IGCTR")
      )
      (libsource (lib "eagle-import") (part "B38G3RGB"))
    )
    (comp (ref "100")
      (value "B38G3RGB")
      (footprint "eagle-import:B38G3RGB")
      (fields
        (field (name "ARROW_PART_NUMBER") "SML-LX0606IGC-TR")
        (field (name "MOUSER_PART_NUMBER") "696-SML-0606IGCTR")
      )
      (libsource (lib "eagle-import") (part "B38G3RGB"))
    )
    (comp (ref "101")
      (value "B38G3RGB")
      (footprint "eagle-import:B38G3RGB")
      (fields
        (field (name "ARROW_PART_NUMBER") "SML-LX0606IGC-TR")
        (field (name "MOUSER_PART_NUMBER") "696-SML-0606IGCTR")
      )
      (libsource (lib "eagle-import") (part "B38G3RGB"))
    )
    (comp (ref "102")
      (value "B38G3RGB")
      (footprint "eagle-import:B38G3RGB")
      (fields
        (field (name "ARROW_PART_NUMBER") "SML-LX0606IGC-TR")
        (field (name "MOUSER_PART_NUMBER") "696-SML-0606IGCTR")
      )
      (libsource (lib "eagle-import") (part "B38G3RGB"))
    )
    (comp (ref "103")
      (value "B38G3RGB")
      (footprint "eagle-import:B38G3RGB")
      (fields
        (field (name "ARROW_PART_NUMBER") "SML-LX0606IGC-TR")
        (field (name "MOUSER_PART_NUMBER") "696-SML-0606IGCTR")
      )
      (libsource (lib "eagle-import") (part "B38G3RGB"))
    )
    (comp (ref "104")
      (value "B38G3RGB")
      (footprint "eagle-import:B38G3RGB")
      (fields
        (field (name "ARROW_PART_NUMBER") "SML-LX0606IGC-TR")
        (field (name "MOUSER_PART_NUMBER") "696-SML-0606IGCTR")
      )
      (libsource (lib "eagle-import") (part "B38G3RGB"))
    )
    (comp (ref "105")
      (value "B38G3RGB")
      (footprint "eagle-import:B38G3RGB")
      (fields
        (field (name "ARROW_PART_NUMBER") "SML-LX0606IGC-TR")
        (field (name "MOUSER_PART_NUMBER") "696-SML-0606IGCTR")
      )
      (libsource (lib "eagle-import") (part "B38G3RGB"))
    )
    (comp (ref "106")
      (value "B38G3RGB")
      (footprint "eagle-import:B38G3RGB")
      (fields
        (field (name "ARROW_PART_NUMBER") "SML-LX0606IGC-TR")
        (field (name "MOUSER_PART_NUMBER") "696-SML-0606IGCTR")
      )
      (libsource (lib "eagle-import") (part "B38G3RGB"))
    )
    (comp (ref "107")
      (value "B38G3RGB")
      (footprint "eagle-import:B38G3RGB")
      (fields
        (field (name "ARROW_PART_NUMBER") "SML-LX0606IGC-TR")
        (field (name "MOUSER_PART_NUMBER") "696-SML-0606IGCTR")
      )
      (libsource (lib "eagle-import") (part "B38G3RGB"))
    )
    (comp (ref "108")
      (value "B38G3RGB")
      (footprint "eagle-import:B38G3RGB")
      (fields
        (field (name "ARROW_PART_NUMBER") "SML-LX0606IGC-TR")
        (field (name "MOUSER_PART_NUMBER") "696-SML-0606IGCTR")
      )
      (libsource (lib "eagle-import") (part "B38G3RGB"))
    )
    (comp (ref "109")
      (value "B38G3RGB")
      (footprint "eagle-import:B38G3RGB")
      (fields
        (field (name "ARROW_PART_NUMBER") "SML-LX0606IGC-TR")
        (field (name "MOUSER_PART_NUMBER") "696-SML-0606IGCTR")
      )
      (libsource (lib "eagle-import") (part "B38G3RGB"))
    )
    (comp (ref "110")
      (value "B38G3RGB")
      (footprint "eagle-import:B38G3RGB")
      (fields
        (field (name "ARROW_PART_NUMBER") "SML-LX0606IGC-TR")
        (field (name "MOUSER_PART_NUMBER") "696-SML-0606IGCTR")
      )
      (libsource (lib "eagle-import") (part "B38G3RGB"))
    )
    (comp (ref "111")
      (value "B38G3RGB")
      (footprint "eagle-import:B38G3RGB")
      (fields
        (field (name "ARROW_PART_NUMBER") "SML-LX0606IGC-TR")
        (field (name "MOUSER_PART_NUMBER") "696-SML-0606IGCTR")
      )
      (libsource (lib "eagle-import") (part "B38G3RGB"))
    )
    (comp (ref "112")
      (value "B38G3RGB")
      (footprint "eagle-import:B38G3RGB")
      (fields
        (field (name "ARROW_PART_NUMBER") "SML-LX0606IGC-TR")
        (field (name "MOUSER_PART_NUMBER") "696-SML-0606IGCTR")
      )
      (libsource (lib "eagle-import") (part "B38G3RGB"))
    )
    (comp (ref "113")
      (value "B38G3RGB")
      (footprint "eagle-import:B38G3RGB")
      (fields
        (field (name "ARROW_PART_NUMBER") "SML-LX0606IGC-TR")
        (field (name "MOUSER_PART_NUMBER") "696-SML-0606IGCTR")
      )
      (libsource (lib "eagle-import") (part "B38G3RGB"))
    )
    (comp (ref "114")
      (value "B38G3RGB")
      (footprint "eagle-import:B38G3RGB")
      (fields
        (field (name "ARROW_PART_NUMBER") "SML-LX0606IGC-TR")
        (field (name "MOUSER_PART_NUMBER") "696-SML-0606IGCTR")
      )
      (libsource (lib "eagle-import") (part "B38G3RGB"))
    )
    (comp (ref "115")
      (value "B38G3RGB")
      (footprint "eagle-import:B38G3RGB")
      (fields
        (field (name "ARROW_PART_NUMBER") "SML-LX0606IGC-TR")
        (field (name "MOUSER_PART_NUMBER") "696-SML-0606IGCTR")
      )
      (libsource (lib "eagle-import") (part "B38G3RGB"))
    )
    (comp (ref "116")
      (value "B38G3RGB")
      (footprint "eagle-import:B38G3RGB")
      (fields
        (field (name "ARROW_PART_NUMBER") "SML-LX0606IGC-TR")
        (field (name "MOUSER_PART_NUMBER") "696-SML-0606IGCTR")
      )
      (libsource (lib "eagle-import") (part "B38G3RGB"))
    )
    (comp (ref "117")
      (value "B38G3RGB")
      (footprint "eagle-import:B38G3RGB")
      (fields
        (field (name "ARROW_PART_NUMBER") "SML-LX0606IGC-TR")
        (field (name "MOUSER_PART_NUMBER") "696-SML-0606IGCTR")
      )
      (libsource (lib "eagle-import") (part "B38G3RGB"))
    )
    (comp (ref "118")
      (value "B38G3RGB")
      (footprint "eagle-import:B38G3RGB")
      (fields
        (field (name "ARROW_PART_NUMBER") "SML-LX0606IGC-TR")
        (field (name "MOUSER_PART_NUMBER") "696-SML-0606IGCTR")
      )
      (libsource (lib "eagle-import") (part "B38G3RGB"))
    )
    (comp (ref "119")
      (value "B38G3RGB")
      (footprint "eagle-import:B38G3RGB")
      (fields
        (field (name "ARROW_PART_NUMBER") "SML-LX0606IGC-TR")
        (field (name "MOUSER_PART_NUMBER") "696-SML-0606IGCTR")
      )
      (libsource (lib "eagle-import") (part "B38G3RGB"))
    )
    (comp (ref "120")
      (value "B38G3RGB")
      (footprint "eagle-import:B38G3RGB")
      (fields
        (field (name "ARROW_PART_NUMBER") "SML-LX0606IGC-TR")
        (field (name "MOUSER_PART_NUMBER") "696-SML-0606IGCTR")
      )
      (libsource (lib "eagle-import") (part "B38G3RGB"))
    )
    (comp (ref "C1")
      (value ".1uF")
      (footprint "eagle-import:C0402")
      (libsource (lib "eagle-import") (part "C-EUC0402"))
    )
    (comp (ref "C1B")
      (value "10uF")
      (footprint "eagle-import:C0402")
      (libsource (lib "eagle-import") (part "C-EUC0402"))
    )
    (comp (ref "C2")
      (value ".1uF")
      (footprint "eagle-import:C0402")
      (libsource (lib "eagle-import") (part "C-EUC0402"))
    )
    (comp (ref "C2B")
      (value "10uF")
      (footprint "eagle-import:C0402")
      (libsource (lib "eagle-import") (part "C-EUC0402"))
    )
    (comp (ref "C3")
      (value ".1uF")
      (footprint "eagle-import:C0402")
      (libsource (lib "eagle-import") (part "C-EUC0402"))
    )
    (comp (ref "C3B")
      (value "10uF")
      (footprint "eagle-import:C0402")
      (libsource (lib "eagle-import") (part "C-EUC0402"))
    )
    (comp (ref "C4")
      (value ".1uF")
      (footprint "eagle-import:C0402")
      (libsource (lib "eagle-import") (part "C-EUC0402"))
    )
    (comp (ref "C4B")
      (value "10uF")
      (footprint "eagle-import:C0402")
      (libsource (lib "eagle-import") (part "C-EUC0402"))
    )
    (comp (ref "C5")
      (value ".1uF")
      (footprint "eagle-import:C0402")
      (libsource (lib "eagle-import") (part "C-EUC0402"))
    )
    (comp (ref "C5B")
      (value "10uF")
      (footprint "eagle-import:C0402")
      (libsource (lib "eagle-import") (part "C-EUC0402"))
    )
    (comp (ref "C6")
      (value ".1uF")
      (footprint "eagle-import:C0402")
      (libsource (lib "eagle-import") (part "C-EUC0402"))
    )
    (comp (ref "C6B")
      (value "10uF")
      (footprint "eagle-import:C0402")
      (libsource (lib "eagle-import") (part "C-EUC0402"))
    )
    (comp (ref "C7")
      (value ".1uF")
      (footprint "eagle-import:C0402")
      (libsource (lib "eagle-import") (part "C-EUC0402"))
    )
    (comp (ref "C7B")
      (value "10uF")
      (footprint "eagle-import:C0402")
      (libsource (lib "eagle-import") (part "C-EUC0402"))
    )
    (comp (ref "C8")
      (value ".1uF")
      (footprint "eagle-import:C0402")
      (libsource (lib "eagle-import") (part "C-EUC0402"))
    )
    (comp (ref "C8B")
      (value "10uF")
      (footprint "eagle-import:C0402")
      (libsource (lib "eagle-import") (part "C-EUC0402"))
    )
    (comp (ref "C28")
      (value "0.1u")
      (footprint "eagle-import:C0402")
      (libsource (lib "eagle-import") (part "C-EUC0402"))
    )
    (comp (ref "C29")
      (value "4.7u")
      (footprint "eagle-import:C0402")
      (libsource (lib "eagle-import") (part "C-EUC0402"))
    )
    (comp (ref "C30")
      (value "0.1u")
      (footprint "eagle-import:C0402")
      (libsource (lib "eagle-import") (part "C-EUC0402"))
    )
    (comp (ref "C31")
      (value "4.7u")
      (footprint "eagle-import:C0402")
      (libsource (lib "eagle-import") (part "C-EUC0402"))
    )
    (comp (ref "C32")
      (value "0.1u")
      (footprint "eagle-import:C0402")
      (libsource (lib "eagle-import") (part "C-EUC0402"))
    )
    (comp (ref "C33")
      (value "4.7u")
      (footprint "eagle-import:C0402")
      (libsource (lib "eagle-import") (part "C-EUC0402"))
    )
    (comp (ref "IC1")
      (value "TLC5955DCAR")
      (footprint "eagle-import:SOP50P810X120-57N")
      (fields (field (name "MOUSER_PART_NUMBER") "595-TLC5955DCAR"))
      (libsource (lib "eagle-import") (part "TLC5955DCAR"))
    )
    (comp (ref "IC2")
      (value "TLC5955DCAR")
      (footprint "eagle-import:SOP50P810X120-57N")
      (fields (field (name "MOUSER_PART_NUMBER") "595-TLC5955DCAR"))
      (libsource (lib "eagle-import") (part "TLC5955DCAR"))
    )
    (comp (ref "IC3")
      (value "TLC5955DCAR")
      (footprint "eagle-import:SOP50P810X120-57N")
      (fields (field (name "MOUSER_PART_NUMBER") "595-TLC5955DCAR"))
      (libsource (lib "eagle-import") (part "TLC5955DCAR"))
    )
    (comp (ref "IC4")
      (value "TLC5955DCAR")
      (footprint "eagle-import:SOP50P810X120-57N")
      (fields (field (name "MOUSER_PART_NUMBER") "595-TLC5955DCAR"))
      (libsource (lib "eagle-import") (part "TLC5955DCAR"))
    )
    (comp (ref "IC5")
      (value "TLC5955DCAR")
      (footprint "eagle-import:SOP50P810X120-57N")
      (fields (field (name "MOUSER_PART_NUMBER") "595-TLC5955DCAR"))
      (libsource (lib "eagle-import") (part "TLC5955DCAR"))
    )
    (comp (ref "IC6")
      (value "TLC5955DCAR")
      (footprint "eagle-import:SOP50P810X120-57N")
      (fields (field (name "MOUSER_PART_NUMBER") "595-TLC5955DCAR"))
      (libsource (lib "eagle-import") (part "TLC5955DCAR"))
    )
    (comp (ref "IC7")
      (value "TLC5955DCAR")
      (footprint "eagle-import:SOP50P810X120-57N")
      (fields (field (name "MOUSER_PART_NUMBER") "595-TLC5955DCAR"))
      (libsource (lib "eagle-import") (part "TLC5955DCAR"))
    )
    (comp (ref "IC8")
      (value "TLC5955DCAR")
      (footprint "eagle-import:SOP50P810X120-57N")
      (fields (field (name "MOUSER_PART_NUMBER") "595-TLC5955DCAR"))
      (libsource (lib "eagle-import") (part "TLC5955DCAR"))
    )
    (comp (ref "IC9")
      (value "SN74LVC1G34DBVR")
      (footprint "eagle-import:SOT95P280X145-5N")
      (fields (field (name "MOUSER_PART_NUMBER") "595-SN74LVC1G34DBVR"))
      (libsource (lib "eagle-import") (part "SN74LVC1G34DBVR"))
    )
    (comp (ref "IC10")
      (value "SN74LVC1G34DBVR")
      (footprint "eagle-import:SOT95P280X145-5N")
      (fields (field (name "MOUSER_PART_NUMBER") "595-SN74LVC1G34DBVR"))
      (libsource (lib "eagle-import") (part "SN74LVC1G34DBVR"))
    )
    (comp (ref "IC11")
      (value "SN74LVC1G34DBVR")
      (footprint "eagle-import:SOT95P280X145-5N")
      (fields (field (name "MOUSER_PART_NUMBER") "595-SN74LVC1G34DBVR"))
      (libsource (lib "eagle-import") (part "SN74LVC1G34DBVR"))
    )
    (comp (ref "SV1")
      (value "MA06-2")
      (footprint "eagle-import:MA06-2")
      (libsource (lib "eagle-import") (part "MA06-2"))
    )
  )
  (nets
    (net (code "1") (name "/3V3") (class "Default")
      (node (ref "1") (pin "3") (pinfunction "COM_3") (pintype "bidirectional"))
      (node (ref "10") (pin "3") (pinfunction "COM_3") (pintype "bidirectional"))
      (node (ref "100") (pin "3") (pinfunction "COM_3") (pintype "bidirectional"))
      (node (ref "101") (pin "3") (pinfunction "COM_3") (pintype "bidirectional"))
      (node (ref "102") (pin "3") (pinfunction "COM_3") (pintype "bidirectional"))
      (node (ref "103") (pin "3") (pinfunction "COM_3") (pintype "bidirectional"))
      (node (ref "104") (pin "3") (pinfunction "COM_3") (pintype "bidirectional"))
      (node (ref "105") (pin "3") (pinfunction "COM_3") (pintype "bidirectional"))
      (node (ref "106") (pin "3") (pinfunction "COM_3") (pintype "bidirectional"))
      (node (ref "107") (pin "3") (pinfunction "COM_3") (pintype "bidirectional"))
      (node (ref "108") (pin "3") (pinfunction "COM_3") (pintype "bidirectional"))
      (node (ref "109") (pin "3") (pinfunction "COM_3") (pintype "bidirectional"))
      (node (ref "11") (pin "3") (pinfunction "COM_3") (pintype "bidirectional"))
      (node (ref "110") (pin "3") (pinfunction "COM_3") (pintype "bidirectional"))
      (node (ref "111") (pin "3") (pinfunction "COM_3") (pintype "bidirectional"))
      (node (ref "112") (pin "3") (pinfunction "COM_3") (pintype "bidirectional"))
      (node (ref "113") (pin "3") (pinfunction "COM_3") (pintype "bidirectional"))
      (node (ref "114") (pin "3") (pinfunction "COM_3") (pintype "bidirectional"))
      (node (ref "115") (pin "3") (pinfunction "COM_3") (pintype "bidirectional"))
      (node (ref "116") (pin "3") (pinfunction "COM_3") (pintype "bidirectional"))
      (node (ref "117") (pin "3") (pinfunction "COM_3") (pintype "bidirectional"))
      (node (ref "118") (pin "3") (pinfunction "COM_3") (pintype "bidirectional"))
      (node (ref "119") (pin "3") (pinfunction "COM_3") (pintype "bidirectional"))
      (node (ref "12") (pin "3") (pinfunction "COM_3") (pintype "bidirectional"))
      (node (ref "120") (pin "3") (pinfunction "COM_3") (pintype "bidirectional"))
      (node (ref "13") (pin "3") (pinfunction "COM_3") (pintype "bidirectional"))
      (node (ref "14") (pin "3") (pinfunction "COM_3") (pintype "bidirectional"))
      (node (ref "15") (pin "3") (pinfunction "COM_3") (pintype "bidirectional"))
      (node (ref "16") (pin "3") (pinfunction "COM_3") (pintype "bidirectional"))
      (node (ref "17") (pin "3") (pinfunction "COM_3") (pintype "bidirectional"))
      (node (ref "18") (pin "3") (pinfunction "COM_3") (pintype "bidirectional"))
      (node (ref "19") (pin "3") (pinfunction "COM_3") (pintype "bidirectional"))
      (node (ref "2") (pin "3") (pinfunction "COM_3") (pintype "bidirectional"))
      (node (ref "20") (pin "3") (pinfunction "COM_3") (pintype "bidirectional"))
      (node (ref "21") (pin "3") (pinfunction "COM_3") (pintype "bidirectional"))
      (node (ref "22") (pin "3") (pinfunction "COM_3") (pintype "bidirectional"))
      (node (ref "23") (pin "3") (pinfunction "COM_3") (pintype "bidirectional"))
      (node (ref "24") (pin "3") (pinfunction "COM_3") (pintype "bidirectional"))
      (node (ref "25") (pin "3") (pinfunction "COM_3") (pintype "bidirectional"))
      (node (ref "26") (pin "3") (pinfunction "COM_3") (pintype "bidirectional"))
      (node (ref "27") (pin "3") (pinfunction "COM_3") (pintype "bidirectional"))
      (node (ref "28") (pin "3") (pinfunction "COM_3") (pintype "bidirectional"))
      (node (ref "29") (pin "3") (pinfunction "COM_3") (pintype "bidirectional"))
      (node (ref "3") (pin "3") (pinfunction "COM_3") (pintype "bidirectional"))
      (node (ref "30") (pin "3") (pinfunction "COM_3") (pintype "bidirectional"))
      (node (ref "31") (pin "3") (pinfunction "COM_3") (pintype "bidirectional"))
      (node (ref "32") (pin "3") (pinfunction "COM_3") (pintype "bidirectional"))
      (node (ref "33") (pin "3") (pinfunction "COM_3") (pintype "bidirectional"))
      (node (ref "34") (pin "3") (pinfunction "COM_3") (pintype "bidirectional"))
      (node (ref "35") (pin "3") (pinfunction "COM_3") (pintype "bidirectional"))
      (node (ref "36") (pin "3") (pinfunction "COM_3") (pintype "bidirectional"))
      (node (ref "37") (pin "3") (pinfunction "COM_3") (pintype "bidirectional"))
      (node (ref "38") (pin "3") (pinfunction "COM_3") (pintype "bidirectional"))
      (node (ref "39") (pin "3") (pinfunction "COM_3") (pintype "bidirectional"))
      (node (ref "4") (pin "3") (pinfunction "COM_3") (pintype "bidirectional"))
      (node (ref "40") (pin "3") (pinfunction "COM_3") (pintype "bidirectional"))
      (node (ref "41") (pin "3") (pinfunction "COM_3") (pintype "bidirectional"))
      (node (ref "42") (pin "3") (pinfunction "COM_3") (pintype "bidirectional"))
      (node (ref "43") (pin "3") (pinfunction "COM_3") (pintype "bidirectional"))
      (node (ref "44") (pin "3") (pinfunction "COM_3") (pintype "bidirectional"))
      (node (ref "45") (pin "3") (pinfunction "COM_3") (pintype "bidirectional"))
      (node (ref "46") (pin "3") (pinfunction "COM_3") (pintype "bidirectional"))
      (node (ref "47") (pin "3") (pinfunction "COM_3") (pintype "bidirectional"))
      (node (ref "48") (pin "3") (pinfunction "COM_3") (pintype "bidirectional"))
      (node (ref "49") (pin "3") (pinfunction "COM_3") (pintype "bidirectional"))
      (node (ref "5") (pin "3") (pinfunction "COM_3") (pintype "bidirectional"))
      (node (ref "50") (pin "3") (pinfunction "COM_3") (pintype "bidirectional"))
      (node (ref "51") (pin "3") (pinfunction "COM_3") (pintype "bidirectional"))
      (node (ref "52") (pin "3") (pinfunction "COM_3") (pintype "bidirectional"))
      (node (ref "53") (pin "3") (pinfunction "COM_3") (pintype "bidirectional"))
      (node (ref "54") (pin "3") (pinfunction "COM_3") (pintype "bidirectional"))
      (node (ref "55") (pin "3") (pinfunction "COM_3") (pintype "bidirectional"))
      (node (ref "56") (pin "3") (pinfunction "COM_3") (pintype "bidirectional"))
      (node (ref "57") (pin "3") (pinfunction "COM_3") (pintype "bidirectional"))
      (node (ref "58") (pin "3") (pinfunction "COM_3") (pintype "bidirectional"))
      (node (ref "59") (pin "3") (pinfunction "COM_3") (pintype "bidirectional"))
      (node (ref "6") (pin "3") (pinfunction "COM_3") (pintype "bidirectional"))
      (node (ref "60") (pin "3") (pinfunction "COM_3") (pintype "bidirectional"))
      (node (ref "61") (pin "3") (pinfunction "COM_3") (pintype "bidirectional"))
      (node (ref "62") (pin "3") (pinfunction "COM_3") (pintype "bidirectional"))
      (node (ref "63") (pin "3") (pinfunction "COM_3") (pintype "bidirectional"))
      (node (ref "64") (pin "3") (pinfunction "COM_3") (pintype "bidirectional"))
      (node (ref "65") (pin "3") (pinfunction "COM_3") (pintype "bidirectional"))
      (node (ref "66") (pin "3") (pinfunction "COM_3") (pintype "bidirectional"))
      (node (ref "67") (pin "3") (pinfunction "COM_3") (pintype "bidirectional"))
      (node (ref "68") (pin "3") (pinfunction "COM_3") (pintype "bidirectional"))
      (node (ref "69") (pin "3") (pinfunction "COM_3") (pintype "bidirectional"))
      (node (ref "7") (pin "3") (pinfunction "COM_3") (pintype "bidirectional"))
      (node (ref "70") (pin "3") (pinfunction "COM_3") (pintype "bidirectional"))
      (node (ref "71") (pin "3") (pinfunction "COM_3") (pintype "bidirectional"))
      (node (ref "72") (pin "3") (pinfunction "COM_3") (pintype "bidirectional"))
      (node (ref "73") (pin "3") (pinfunction "COM_3") (pintype "bidirectional"))
      (node (ref "74") (pin "3") (pinfunction "COM_3") (pintype "bidirectional"))
      (node (ref "75") (pin "3") (pinfunction "COM_3") (pintype "bidirectional"))
      (node (ref "76") (pin "3") (pinfunction "COM_3") (pintype "bidirectional"))
      (node (ref "77") (pin "3") (pinfunction "COM_3") (pintype "bidirectional"))
      (node (ref "78") (pin "3") (pinfunction "COM_3") (pintype "bidirectional"))
      (node (ref "79") (pin "3") (pinfunction "COM_3") (pintype "bidirectional"))
      (node (ref "8") (pin "3") (pinfunction "COM_3") (pintype "bidirectional"))
      (node (ref "80") (pin "3") (pinfunction "COM_3") (pintype "bidirectional"))
      (node (ref "81") (pin "3") (pinfunction "COM_3") (pintype "bidirectional"))
      (node (ref "82") (pin "3") (pinfunction "COM_3") (pintype "bidirectional"))
      (node (ref "83") (pin "3") (pinfunction "COM_3") (pintype "bidirectional"))
      (node (ref "84") (pin "3") (pinfunction "COM_3") (pintype "bidirectional"))
      (node (ref "85") (pin "3") (pinfunction "COM_3") (pintype "bidirectional"))
      (node (ref "86") (pin "3") (pinfunction "COM_3") (pintype "bidirectional"))
      (node (ref "87") (pin "3") (pinfunction "COM_3") (pintype "bidirectional"))
      (node (ref "88") (pin "3") (pinfunction "COM_3") (pintype "bidirectional"))
      (node (ref "89") (pin "3") (pinfunction "COM_3") (pintype "bidirectional"))
      (node (ref "9") (pin "3") (pinfunction "COM_3") (pintype "bidirectional"))
      (node (ref "90") (pin "3") (pinfunction "COM_3") (pintype "bidirectional"))
      (node (ref "91") (pin "3") (pinfunction "COM_3") (pintype "bidirectional"))
      (node (ref "92") (pin "3") (pinfunction "COM_3") (pintype "bidirectional"))
      (node (ref "93") (pin "3") (pinfunction "COM_3") (pintype "bidirectional"))
      (node (ref "94") (pin "3") (pinfunction "COM_3") (pintype "bidirectional"))
      (node (ref "95") (pin "3") (pinfunction "COM_3") (pintype "bidirectional"))
      (node (ref "96") (pin "3") (pinfunction "COM_3") (pintype "bidirectional"))
      (node (ref "97") (pin "3") (pinfunction "COM_3") (pintype "bidirectional"))
      (node (ref "98") (pin "3") (pinfunction "COM_3") (pintype "bidirectional"))
      (node (ref "99") (pin "3") (pinfunction "COM_3") (pintype "bidirectional"))
      (node (ref "SV1") (pin "6") (pinfunction "6_6") (pintype "passive"))
      (node (ref "SV1") (pin "8") (pinfunction "8_8") (pintype "passive"))
    )
    (net (code "2") (name "/GND") (class "Default")
      (node (ref "C1") (pin "2") (pinfunction "2_2") (pintype "passive"))
      (node (ref "C1B") (pin "2") (pinfunction "2_2") (pintype "passive"))
      (node (ref "C2") (pin "2") (pinfunction "2_2") (pintype "passive"))
      (node (ref "C28") (pin "2") (pinfunction "2_2") (pintype "passive"))
      (node (ref "C29") (pin "2") (pinfunction "2_2") (pintype "passive"))
      (node (ref "C2B") (pin "2") (pinfunction "2_2") (pintype "passive"))
      (node (ref "C3") (pin "2") (pinfunction "2_2") (pintype "passive"))
      (node (ref "C30") (pin "2") (pinfunction "2_2") (pintype "passive"))
      (node (ref "C31") (pin "2") (pinfunction "2_2") (pintype "passive"))
      (node (ref "C32") (pin "2") (pinfunction "2_2") (pintype "passive"))
      (node (ref "C33") (pin "2") (pinfunction "2_2") (pintype "passive"))
      (node (ref "C3B") (pin "2") (pinfunction "2_2") (pintype "passive"))
      (node (ref "C4") (pin "2") (pinfunction "2_2") (pintype "passive"))
      (node (ref "C4B") (pin "2") (pinfunction "2_2") (pintype "passive"))
      (node (ref "C5") (pin "2") (pinfunction "2_2") (pintype "passive"))
      (node (ref "C5B") (pin "2") (pinfunction "2_2") (pintype "passive"))
      (node (ref "C6") (pin "2") (pinfunction "2_2") (pintype "passive"))
      (node (ref "C6B") (pin "2") (pinfunction "2_2") (pintype "passive"))
      (node (ref "C7") (pin "2") (pinfunction "2_2") (pintype "passive"))
      (node (ref "C7B") (pin "2") (pinfunction "2_2") (pintype "passive"))
      (node (ref "C8") (pin "2") (pinfunction "2_2") (pintype "passive"))
      (node (ref "C8B") (pin "2") (pinfunction "2_2") (pintype "passive"))
      (node (ref "IC1") (pin "29") (pinfunction "GND_1_29") (pintype "bidirectional"))
      (node (ref "IC1") (pin "56") (pinfunction "GND_2_56") (pintype "bidirectional"))
      (node (ref "IC1") (pin "57") (pinfunction "THERMALPAD_57") (pintype "bidirectional"))
      (node (ref "IC10") (pin "3") (pinfunction "GND_3") (pintype "bidirectional"))
      (node (ref "IC11") (pin "3") (pinfunction "GND_3") (pintype "bidirectional"))
      (node (ref "IC2") (pin "29") (pinfunction "GND_1_29") (pintype "bidirectional"))
      (node (ref "IC2") (pin "56") (pinfunction "GND_2_56") (pintype "bidirectional"))
      (node (ref "IC2") (pin "57") (pinfunction "THERMALPAD_57") (pintype "bidirectional"))
      (node (ref "IC3") (pin "29") (pinfunction "GND_1_29") (pintype "bidirectional"))
      (node (ref "IC3") (pin "56") (pinfunction "GND_2_56") (pintype "bidirectional"))
      (node (ref "IC3") (pin "57") (pinfunction "THERMALPAD_57") (pintype "bidirectional"))
      (node (ref "IC4") (pin "29") (pinfunction "GND_1_29") (pintype "bidirectional"))
      (node (ref "IC4") (pin "56") (pinfunction "GND_2_56") (pintype "bidirectional"))
      (node (ref "IC4") (pin "57") (pinfunction "THERMALPAD_57") (pintype "bidirectional"))
      (node (ref "IC5") (pin "29") (pinfunction "GND_1_29") (pintype "bidirectional"))
      (node (ref "IC5") (pin "56") (pinfunction "GND_2_56") (pintype "bidirectional"))
      (node (ref "IC5") (pin "57") (pinfunction "THERMALPAD_57") (pintype "bidirectional"))
      (node (ref "IC6") (pin "29") (pinfunction "GND_1_29") (pintype "bidirectional"))
      (node (ref "IC6") (pin "56") (pinfunction "GND_2_56") (pintype "bidirectional"))
      (node (ref "IC6") (pin "57") (pinfunction "THERMALPAD_57") (pintype "bidirectional"))
      (node (ref "IC7") (pin "29") (pinfunction "GND_1_29") (pintype "bidirectional"))
      (node (ref "IC7") (pin "56") (pinfunction "GND_2_56") (pintype "bidirectional"))
      (node (ref "IC7") (pin "57") (pinfunction "THERMALPAD_57") (pintype "bidirectional"))
      (node (ref "IC8") (pin "29") (pinfunction "GND_1_29") (pintype "bidirectional"))
      (node (ref "IC8") (pin "56") (pinfunction "GND_2_56") (pintype "bidirectional"))
      (node (ref "IC8") (pin "57") (pinfunction "THERMALPAD_57") (pintype "bidirectional"))
      (node (ref "IC9") (pin "3") (pinfunction "GND_3") (pintype "bidirectional"))
      (node (ref "SV1") (pin "2") (pinfunction "2_2") (pintype "passive"))
      (node (ref "SV1") (pin "4") (pinfunction "4_4") (pintype "passive"))
    )
    (net (code "3") (name "/N$352") (class "Default")
      (node (ref "IC8") (pin "53") (pinfunction "OUTB8_53") (pintype "bidirectional"))
    )
    (net (code "4") (name "/N$353") (class "Default")
      (node (ref "IC8") (pin "52") (pinfunction "OUTR8_52") (pintype "bidirectional"))
    )
    (net (code "5") (name "/N$354") (class "Default")
      (node (ref "IC8") (pin "51") (pinfunction "OUTG8_51") (pintype "bidirectional"))
    )
    (net (code "6") (name "/N$355") (class "Default")
      (node (ref "IC8") (pin "50") (pinfunction "OUTB12_50") (pintype "bidirectional"))
    )
    (net (code "7") (name "/N$356") (class "Default")
      (node (ref "IC8") (pin "49") (pinfunction "OUTR12_49") (pintype "bidirectional"))
    )
    (net (code "8") (name "/N$357") (class "Default")
      (node (ref "IC8") (pin "48") (pinfunction "OUTG12_48") (pintype "bidirectional"))
    )
    (net (code "9") (name "/N$358") (class "Default")
      (node (ref "IC8") (pin "47") (pinfunction "OUTB9_47") (pintype "bidirectional"))
    )
    (net (code "10") (name "/N$359") (class "Default")
      (node (ref "IC8") (pin "46") (pinfunction "OUTR9_46") (pintype "bidirectional"))
    )
    (net (code "11") (name "/N$360") (class "Default")
      (node (ref "IC8") (pin "45") (pinfunction "OUTG9_45") (pintype "bidirectional"))
    )
    (net (code "12") (name "/N$361") (class "Default")
      (node (ref "IC8") (pin "44") (pinfunction "OUTB13_44") (pintype "bidirectional"))
    )
    (net (code "13") (name "/N$362") (class "Default")
      (node (ref "IC8") (pin "43") (pinfunction "OUTR13_43") (pintype "bidirectional"))
    )
    (net (code "14") (name "/N$363") (class "Default")
      (node (ref "IC8") (pin "42") (pinfunction "OUTG13_42") (pintype "bidirectional"))
    )
    (net (code "15") (name "/N$IC8_PIN4") (class "Default")
      (node (ref "IC8") (pin "4") (pinfunction "OUTB4_4") (pintype "bidirectional"))
    )
    (net (code "16") (name "/N$IC8_PIN5") (class "Default")
      (node (ref "IC8") (pin "5") (pinfunction "OUTR4_5") (pintype "bidirectional"))
    )
    (net (code "17") (name "/N$IC8_PIN6") (class "Default")
      (node (ref "IC8") (pin "6") (pinfunction "OUTG4_6") (pintype "bidirectional"))
    )
    (net (code "18") (name "/N$IC8_PIN7") (class "Default")
      (node (ref "IC8") (pin "7") (pinfunction "OUTB0_7") (pintype "bidirectional"))
    )
    (net (code "19") (name "/N$IC8_PIN8") (class "Default")
      (node (ref "IC8") (pin "8") (pinfunction "OUTR0_8") (pintype "bidirectional"))
    )
    (net (code "20") (name "/N$IC8_PIN9") (class "Default")
      (node (ref "IC8") (pin "9") (pinfunction "OUTG0_9") (pintype "bidirectional"))
    )
    (net (code "21") (name "/N$IC8_PIN10") (class "Default")
      (node (ref "IC8") (pin "10") (pinfunction "OUTB5_10") (pintype "bidirectional"))
    )
    (net (code "22") (name "/N$IC8_PIN11") (class "Default")
      (node (ref "IC8") (pin "11") (pinfunction "OUTR5_11") (pintype "bidirectional"))
    )
    (net (code "23") (name "/N$IC8_PIN12") (class "Default")
      (node (ref "IC8") (pin "12") (pinfunction "OUTG5_12") (pintype "bidirectional"))
    )
    (net (code "24") (name "/N$IC8_PIN13") (class "Default")
      (node (ref "IC8") (pin "13") (pinfunction "OUTB1_13") (pintype "bidirectional"))
    )
    (net (code "25") (name "/N$IC8_PIN14") (class "Default")
      (node (ref "IC8") (pin "14") (pinfunction "OUTR1_14") (pintype "bidirectional"))
    )
    (net (code "26") (name "/N$IC8_PIN15") (class "Default")
      (node (ref "IC8") (pin "15") (pinfunction "OUTG1_15") (pintype "bidirectional"))
    )
    (net (code "27") (name "/N$LEDB1") (class "Default")
      (node (ref "1") (pin "2") (pinfunction "BLUE_2") (pintype "bidirectional"))
      (node (ref "IC1") (pin "25") (pinfunction "OUTB7_25") (pintype "bidirectional"))
    )
    (net (code "28") (name "/N$LEDB2") (class "Default")
      (node (ref "2") (pin "2") (pinfunction "BLUE_2") (pintype "bidirectional"))
      (node (ref "IC1") (pin "22") (pinfunction "OUTB3_22") (pintype "bidirectional"))
    )
    (net (code "29") (name "/N$LEDB3") (class "Default")
      (node (ref "3") (pin "2") (pinfunction "BLUE_2") (pintype "bidirectional"))
      (node (ref "IC1") (pin "32") (pinfunction "OUTB11_32") (pintype "bidirectional"))
    )
    (net (code "30") (name "/N$LEDB4") (class "Default")
      (node (ref "4") (pin "2") (pinfunction "BLUE_2") (pintype "bidirectional"))
      (node (ref "IC1") (pin "35") (pinfunction "OUTB15_35") (pintype "bidirectional"))
    )
    (net (code "31") (name "/N$LEDB5") (class "Default")
      (node (ref "5") (pin "2") (pinfunction "BLUE_2") (pintype "bidirectional"))
      (node (ref "IC1") (pin "19") (pinfunction "OUTB6_19") (pintype "bidirectional"))
    )
    (net (code "32") (name "/N$LEDB6") (class "Default")
      (node (ref "6") (pin "2") (pinfunction "BLUE_2") (pintype "bidirectional"))
      (node (ref "IC1") (pin "16") (pinfunction "OUTB2_16") (pintype "bidirectional"))
    )
    (net (code "33") (name "/N$LEDB7") (class "Default")
      (node (ref "7") (pin "2") (pinfunction "BLUE_2") (pintype "bidirectional"))
      (node (ref "IC1") (pin "38") (pinfunction "OUTB10_38") (pintype "bidirectional"))
    )
    (net (code "34") (name "/N$LEDB8") (class "Default")
      (node (ref "8") (pin "2") (pinfunction "BLUE_2") (pintype "bidirectional"))
      (node (ref "IC1") (pin "41") (pinfunction "OUTB14_41") (pintype "bidirectional"))
    )
    (net (code "35") (name "/N$LEDB9") (class "Default")
      (node (ref "9") (pin "2") (pinfunction "BLUE_2") (pintype "bidirectional"))
      (node (ref "IC1") (pin "13") (pinfunction "OUTB1_13") (pintype "bidirectional"))
    )
    (net (code "36") (name "/N$LEDB10") (class "Default")
      (node (ref "10") (pin "2") (pinfunction "BLUE_2") (pintype "bidirectional"))
      (node (ref "IC1") (pin "10") (pinfunction "OUTB5_10") (pintype "bidirectional"))
    )
    (net (code "37") (name "/N$LEDB11") (class "Default")
      (node (ref "11") (pin "2") (pinfunction "BLUE_2") (pintype "bidirectional"))
      (node (ref "IC1") (pin "44") (pinfunction "OUTB13_44") (pintype "bidirectional"))
    )
    (net (code "38") (name "/N$LEDB12") (class "Default")
      (node (ref "12") (pin "2") (pinfunction "BLUE_2") (pintype "bidirectional"))
      (node (ref "IC1") (pin "47") (pinfunction "OUTB9_47") (pintype "bidirectional"))
    )
    (net (code "39") (name "/N$LEDB13") (class "Default")
      (node (ref "13") (pin "2") (pinfunction "BLUE_2") (pintype "bidirectional"))
      (node (ref "IC1") (pin "4") (pinfunction "OUTB4_4") (pintype "bidirectional"))
    )
    (net (code "40") (name "/N$LEDB14") (class "Default")
      (node (ref "14") (pin "2") (pinfunction "BLUE_2") (pintype "bidirectional"))
      (node (ref "IC1") (pin "7") (pinfunction "OUTB0_7") (pintype "bidirectional"))
    )
    (net (code "41") (name "/N$LEDB15") (class "Default")
      (node (ref "15") (pin "2") (pinfunction "BLUE_2") (pintype "bidirectional"))
      (node (ref "IC1") (pin "50") (pinfunction "OUTB12_50") (pintype "bidirectional"))
    )
    (net (code "42") (name "/N$LEDB16") (class "Default")
      (node (ref "16") (pin "2") (pinfunction "BLUE_2") (pintype "bidirectional"))
      (node (ref "IC1") (pin "53") (pinfunction "OUTB8_53") (pintype "bidirectional"))
    )
    (net (code "43") (name "/N$LEDB17") (class "Default")
      (node (ref "17") (pin "2") (pinfunction "BLUE_2") (pintype "bidirectional"))
      (node (ref "IC2") (pin "25") (pinfunction "OUTB7_25") (pintype "bidirectional"))
    )
    (net (code "44") (name "/N$LEDB18") (class "Default")
      (node (ref "18") (pin "2") (pinfunction "BLUE_2") (pintype "bidirectional"))
      (node (ref "IC2") (pin "22") (pinfunction "OUTB3_22") (pintype "bidirectional"))
    )
    (net (code "45") (name "/N$LEDB19") (class "Default")
      (node (ref "19") (pin "2") (pinfunction "BLUE_2") (pintype "bidirectional"))
      (node (ref "IC2") (pin "32") (pinfunction "OUTB11_32") (pintype "bidirectional"))
    )
    (net (code "46") (name "/N$LEDB20") (class "Default")
      (node (ref "20") (pin "2") (pinfunction "BLUE_2") (pintype "bidirectional"))
      (node (ref "IC2") (pin "35") (pinfunction "OUTB15_35") (pintype "bidirectional"))
    )
    (net (code "47") (name "/N$LEDB21") (class "Default")
      (node (ref "21") (pin "2") (pinfunction "BLUE_2") (pintype "bidirectional"))
      (node (ref "IC2") (pin "19") (pinfunction "OUTB6_19") (pintype "bidirectional"))
    )
    (net (code "48") (name "/N$LEDB22") (class "Default")
      (node (ref "22") (pin "2") (pinfunction "BLUE_2") (pintype "bidirectional"))
      (node (ref "IC2") (pin "16") (pinfunction "OUTB2_16") (pintype "bidirectional"))
    )
    (net (code "49") (name "/N$LEDB23") (class "Default")
      (node (ref "23") (pin "2") (pinfunction "BLUE_2") (pintype "bidirectional"))
      (node (ref "IC2") (pin "38") (pinfunction "OUTB10_38") (pintype "bidirectional"))
    )
    (net (code "50") (name "/N$LEDB24") (class "Default")
      (node (ref "24") (pin "2") (pinfunction "BLUE_2") (pintype "bidirectional"))
      (node (ref "IC2") (pin "41") (pinfunction "OUTB14_41") (pintype "bidirectional"))
    )
    (net (code "51") (name "/N$LEDB25") (class "Default")
      (node (ref "25") (pin "2") (pinfunction "BLUE_2") (pintype "bidirectional"))
      (node (ref "IC2") (pin "13") (pinfunction "OUTB1_13") (pintype "bidirectional"))
    )
    (net (code "52") (name "/N$LEDB26") (class "Default")
      (node (ref "26") (pin "2") (pinfunction "BLUE_2") (pintype "bidirectional"))
      (node (ref "IC2") (pin "10") (pinfunction "OUTB5_10") (pintype "bidirectional"))
    )
    (net (code "53") (name "/N$LEDB27") (class "Default")
      (node (ref "27") (pin "2") (pinfunction "BLUE_2") (pintype "bidirectional"))
      (node (ref "IC2") (pin "44") (pinfunction "OUTB13_44") (pintype "bidirectional"))
    )
    (net (code "54") (name "/N$LEDB28") (class "Default")
      (node (ref "28") (pin "2") (pinfunction "BLUE_2") (pintype "bidirectional"))
      (node (ref "IC2") (pin "47") (pinfunction "OUTB9_47") (pintype "bidirectional"))
    )
    (net (code "55") (name "/N$LEDB29") (class "Default")
      (node (ref "29") (pin "2") (pinfunction "BLUE_2") (pintype "bidirectional"))
      (node (ref "IC2") (pin "4") (pinfunction "OUTB4_4") (pintype "bidirectional"))
    )
    (net (code "56") (name "/N$LEDB30") (class "Default")
      (node (ref "30") (pin "2") (pinfunction "BLUE_2") (pintype "bidirectional"))
      (node (ref "IC2") (pin "7") (pinfunction "OUTB0_7") (pintype "bidirectional"))
    )
    (net (code "57") (name "/N$LEDB31") (class "Default")
      (node (ref "31") (pin "2") (pinfunction "BLUE_2") (pintype "bidirectional"))
      (node (ref "IC2") (pin "50") (pinfunction "OUTB12_50") (pintype "bidirectional"))
    )
    (net (code "58") (name "/N$LEDB32") (class "Default")
      (node (ref "32") (pin "2") (pinfunction "BLUE_2") (pintype "bidirectional"))
      (node (ref "IC2") (pin "53") (pinfunction "OUTB8_53") (pintype "bidirectional"))
    )
    (net (code "59") (name "/N$LEDB33") (class "Default")
      (node (ref "33") (pin "2") (pinfunction "BLUE_2") (pintype "bidirectional"))
      (node (ref "IC3") (pin "25") (pinfunction "OUTB7_25") (pintype "bidirectional"))
    )
    (net (code "60") (name "/N$LEDB34") (class "Default")
      (node (ref "34") (pin "2") (pinfunction "BLUE_2") (pintype "bidirectional"))
      (node (ref "IC3") (pin "22") (pinfunction "OUTB3_22") (pintype "bidirectional"))
    )
    (net (code "61") (name "/N$LEDB35") (class "Default")
      (node (ref "35") (pin "2") (pinfunction "BLUE_2") (pintype "bidirectional"))
      (node (ref "IC3") (pin "32") (pinfunction "OUTB11_32") (pintype "bidirectional"))
    )
    (net (code "62") (name "/N$LEDB36") (class "Default")
      (node (ref "36") (pin "2") (pinfunction "BLUE_2") (pintype "bidirectional"))
      (node (ref "IC3") (pin "35") (pinfunction "OUTB15_35") (pintype "bidirectional"))
    )
    (net (code "63") (name "/N$LEDB37") (class "Default")
      (node (ref "37") (pin "2") (pinfunction "BLUE_2") (pintype "bidirectional"))
      (node (ref "IC3") (pin "19") (pinfunction "OUTB6_19") (pintype "bidirectional"))
    )
    (net (code "64") (name "/N$LEDB38") (class "Default")
      (node (ref "38") (pin "2") (pinfunction "BLUE_2") (pintype "bidirectional"))
      (node (ref "IC3") (pin "16") (pinfunction "OUTB2_16") (pintype "bidirectional"))
    )
    (net (code "65") (name "/N$LEDB39") (class "Default")
      (node (ref "39") (pin "2") (pinfunction "BLUE_2") (pintype "bidirectional"))
      (node (ref "IC3") (pin "38") (pinfunction "OUTB10_38") (pintype "bidirectional"))
    )
    (net (code "66") (name "/N$LEDB40") (class "Default")
      (node (ref "40") (pin "2") (pinfunction "BLUE_2") (pintype "bidirectional"))
      (node (ref "IC3") (pin "41") (pinfunction "OUTB14_41") (pintype "bidirectional"))
    )
    (net (code "67") (name "/N$LEDB41") (class "Default")
      (node (ref "41") (pin "2") (pinfunction "BLUE_2") (pintype "bidirectional"))
      (node (ref "IC3") (pin "13") (pinfunction "OUTB1_13") (pintype "bidirectional"))
    )
    (net (code "68") (name "/N$LEDB42") (class "Default")
      (node (ref "42") (pin "2") (pinfunction "BLUE_2") (pintype "bidirectional"))
      (node (ref "IC3") (pin "10") (pinfunction "OUTB5_10") (pintype "bidirectional"))
    )
    (net (code "69") (name "/N$LEDB43") (class "Default")
      (node (ref "43") (pin "2") (pinfunction "BLUE_2") (pintype "bidirectional"))
      (node (ref "IC3") (pin "44") (pinfunction "OUTB13_44") (pintype "bidirectional"))
    )
    (net (code "70") (name "/N$LEDB44") (class "Default")
      (node (ref "44") (pin "2") (pinfunction "BLUE_2") (pintype "bidirectional"))
      (node (ref "IC3") (pin "47") (pinfunction "OUTB9_47") (pintype "bidirectional"))
    )
    (net (code "71") (name "/N$LEDB45") (class "Default")
      (node (ref "45") (pin "2") (pinfunction "BLUE_2") (pintype "bidirectional"))
      (node (ref "IC3") (pin "4") (pinfunction "OUTB4_4") (pintype "bidirectional"))
    )
    (net (code "72") (name "/N$LEDB46") (class "Default")
      (node (ref "46") (pin "2") (pinfunction "BLUE_2") (pintype "bidirectional"))
      (node (ref "IC3") (pin "7") (pinfunction "OUTB0_7") (pintype "bidirectional"))
    )
    (net (code "73") (name "/N$LEDB47") (class "Default")
      (node (ref "47") (pin "2") (pinfunction "BLUE_2") (pintype "bidirectional"))
      (node (ref "IC3") (pin "50") (pinfunction "OUTB12_50") (pintype "bidirectional"))
    )
    (net (code "74") (name "/N$LEDB48") (class "Default")
      (node (ref "48") (pin "2") (pinfunction "BLUE_2") (pintype "bidirectional"))
      (node (ref "IC3") (pin "53") (pinfunction "OUTB8_53") (pintype "bidirectional"))
    )
    (net (code "75") (name "/N$LEDB49") (class "Default")
      (node (ref "49") (pin "2") (pinfunction "BLUE_2") (pintype "bidirectional"))
      (node (ref "IC4") (pin "25") (pinfunction "OUTB7_25") (pintype "bidirectional"))
    )
    (net (code "76") (name "/N$LEDB50") (class "Default")
      (node (ref "50") (pin "2") (pinfunction "BLUE_2") (pintype "bidirectional"))
      (node (ref "IC4") (pin "22") (pinfunction "OUTB3_22") (pintype "bidirectional"))
    )
    (net (code "77") (name "/N$LEDB51") (class "Default")
      (node (ref "51") (pin "2") (pinfunction "BLUE_2") (pintype "bidirectional"))
      (node (ref "IC4") (pin "32") (pinfunction "OUTB11_32") (pintype "bidirectional"))
    )
    (net (code "78") (name "/N$LEDB52") (class "Default")
      (node (ref "52") (pin "2") (pinfunction "BLUE_2") (pintype "bidirectional"))
      (node (ref "IC4") (pin "35") (pinfunction "OUTB15_35") (pintype "bidirectional"))
    )
    (net (code "79") (name "/N$LEDB53") (class "Default")
      (node (ref "53") (pin "2") (pinfunction "BLUE_2") (pintype "bidirectional"))
      (node (ref "IC4") (pin "19") (pinfunction "OUTB6_19") (pintype "bidirectional"))
    )
    (net (code "80") (name "/N$LEDB54") (class "Default")
      (node (ref "54") (pin "2") (pinfunction "BLUE_2") (pintype "bidirectional"))
      (node (ref "IC4") (pin "16") (pinfunction "OUTB2_16") (pintype "bidirectional"))
    )
    (net (code "81") (name "/N$LEDB55") (class "Default")
      (node (ref "55") (pin "2") (pinfunction "BLUE_2") (pintype "bidirectional"))
      (node (ref "IC4") (pin "38") (pinfunction "OUTB10_38") (pintype "bidirectional"))
    )
    (net (code "82") (name "/N$LEDB56") (class "Default")
      (node (ref "56") (pin "2") (pinfunction "BLUE_2") (pintype "bidirectional"))
      (node (ref "IC4") (pin "41") (pinfunction "OUTB14_41") (pintype "bidirectional"))
    )
    (net (code "83") (name "/N$LEDB57") (class "Default")
      (node (ref "57") (pin "2") (pinfunction "BLUE_2") (pintype "bidirectional"))
      (node (ref "IC4") (pin "13") (pinfunction "OUTB1_13") (pintype "bidirectional"))
    )
    (net (code "84") (name "/N$LEDB58") (class "Default")
      (node (ref "58") (pin "2") (pinfunction "BLUE_2") (pintype "bidirectional"))
      (node (ref "IC4") (pin "10") (pinfunction "OUTB5_10") (pintype "bidirectional"))
    )
    (net (code "85") (name "/N$LEDB59") (class "Default")
      (node (ref "59") (pin "2") (pinfunction "BLUE_2") (pintype "bidirectional"))
      (node (ref "IC4") (pin "44") (pinfunction "OUTB13_44") (pintype "bidirectional"))
    )
    (net (code "86") (name "/N$LEDB60") (class "Default")
      (node (ref "60") (pin "2") (pinfunction "BLUE_2") (pintype "bidirectional"))
      (node (ref "IC4") (pin "47") (pinfunction "OUTB9_47") (pintype "bidirectional"))
    )
    (net (code "87") (name "/N$LEDB61") (class "Default")
      (node (ref "61") (pin "2") (pinfunction "BLUE_2") (pintype "bidirectional"))
      (node (ref "IC4") (pin "4") (pinfunction "OUTB4_4") (pintype "bidirectional"))
    )
    (net (code "88") (name "/N$LEDB62") (class "Default")
      (node (ref "62") (pin "2") (pinfunction "BLUE_2") (pintype "bidirectional"))
      (node (ref "IC4") (pin "7") (pinfunction "OUTB0_7") (pintype "bidirectional"))
    )
    (net (code "89") (name "/N$LEDB63") (class "Default")
      (node (ref "63") (pin "2") (pinfunction "BLUE_2") (pintype "bidirectional"))
      (node (ref "IC4") (pin "50") (pinfunction "OUTB12_50") (pintype "bidirectional"))
    )
    (net (code "90") (name "/N$LEDB64") (class "Default")
      (node (ref "64") (pin "2") (pinfunction "BLUE_2") (pintype "bidirectional"))
      (node (ref "IC4") (pin "53") (pinfunction "OUTB8_53") (pintype "bidirectional"))
    )
    (net (code "91") (name "/N$LEDB65") (class "Default")
      (node (ref "65") (pin "2") (pinfunction "BLUE_2") (pintype "bidirectional"))
      (node (ref "IC5") (pin "25") (pinfunction "OUTB7_25") (pintype "bidirectional"))
    )
    (net (code "92") (name "/N$LEDB66") (class "Default")
      (node (ref "66") (pin "2") (pinfunction "BLUE_2") (pintype "bidirectional"))
      (node (ref "IC5") (pin "22") (pinfunction "OUTB3_22") (pintype "bidirectional"))
    )
    (net (code "93") (name "/N$LEDB67") (class "Default")
      (node (ref "67") (pin "2") (pinfunction "BLUE_2") (pintype "bidirectional"))
      (node (ref "IC5") (pin "32") (pinfunction "OUTB11_32") (pintype "bidirectional"))
    )
    (net (code "94") (name "/N$LEDB68") (class "Default")
      (node (ref "68") (pin "2") (pinfunction "BLUE_2") (pintype "bidirectional"))
      (node (ref "IC5") (pin "35") (pinfunction "OUTB15_35") (pintype "bidirectional"))
    )
    (net (code "95") (name "/N$LEDB69") (class "Default")
      (node (ref "69") (pin "2") (pinfunction "BLUE_2") (pintype "bidirectional"))
      (node (ref "IC5") (pin "19") (pinfunction "OUTB6_19") (pintype "bidirectional"))
    )
    (net (code "96") (name "/N$LEDB70") (class "Default")
      (node (ref "70") (pin "2") (pinfunction "BLUE_2") (pintype "bidirectional"))
      (node (ref "IC5") (pin "16") (pinfunction "OUTB2_16") (pintype "bidirectional"))
    )
    (net (code "97") (name "/N$LEDB71") (class "Default")
      (node (ref "71") (pin "2") (pinfunction "BLUE_2") (pintype "bidirectional"))
      (node (ref "IC5") (pin "38") (pinfunction "OUTB10_38") (pintype "bidirectional"))
    )
    (net (code "98") (name "/N$LEDB72") (class "Default")
      (node (ref "72") (pin "2") (pinfunction "BLUE_2") (pintype "bidirectional"))
      (node (ref "IC5") (pin "41") (pinfunction "OUTB14_41") (pintype "bidirectional"))
    )
    (net (code "99") (name "/N$LEDB73") (class "Default")
      (node (ref "73") (pin "2") (pinfunction "BLUE_2") (pintype "bidirectional"))
      (node (ref "IC5") (pin "13") (pinfunction "OUTB1_13") (pintype "bidirectional"))
    )
    (net (code "100") (name "/N$LEDB74") (class "Default")
      (node (ref "74") (pin "2") (pinfunction "BLUE_2") (pintype "bidirectional"))
      (node (ref "IC5") (pin "10") (pinfunction "OUTB5_10") (pintype "bidirectional"))
    )
    (net (code "101") (name "/N$LEDB75") (class "Default")
      (node (ref "75") (pin "2") (pinfunction "BLUE_2") (pintype "bidirectional"))
      (node (ref "IC5") (pin "44") (pinfunction "OUTB13_44") (pintype "bidirectional"))
    )
    (net (code "102") (name "/N$LEDB76") (class "Default")
      (node (ref "76") (pin "2") (pinfunction "BLUE_2") (pintype "bidirectional"))
      (node (ref "IC5") (pin "47") (pinfunction "OUTB9_47") (pintype "bidirectional"))
    )
    (net (code "103") (name "/N$LEDB77") (class "Default")
      (node (ref "77") (pin "2") (pinfunction "BLUE_2") (pintype "bidirectional"))
      (node (ref "IC5") (pin "4") (pinfunction "OUTB4_4") (pintype "bidirectional"))
    )
    (net (code "104") (name "/N$LEDB78") (class "Default")
      (node (ref "78") (pin "2") (pinfunction "BLUE_2") (pintype "bidirectional"))
      (node (ref "IC5") (pin "7") (pinfunction "OUTB0_7") (pintype "bidirectional"))
    )
    (net (code "105") (name "/N$LEDB79") (class "Default")
      (node (ref "79") (pin "2") (pinfunction "BLUE_2") (pintype "bidirectional"))
      (node (ref "IC5") (pin "50") (pinfunction "OUTB12_50") (pintype "bidirectional"))
    )
    (net (code "106") (name "/N$LEDB80") (class "Default")
      (node (ref "80") (pin "2") (pinfunction "BLUE_2") (pintype "bidirectional"))
      (node (ref "IC5") (pin "53") (pinfunction "OUTB8_53") (pintype "bidirectional"))
    )
    (net (code "107") (name "/N$LEDB81") (class "Default")
      (node (ref "81") (pin "2") (pinfunction "BLUE_2") (pintype "bidirectional"))
      (node (ref "IC6") (pin "25") (pinfunction "OUTB7_25") (pintype "bidirectional"))
    )
    (net (code "108") (name "/N$LEDB82") (class "Default")
      (node (ref "82") (pin "2") (pinfunction "BLUE_2") (pintype "bidirectional"))
      (node (ref "IC6") (pin "22") (pinfunction "OUTB3_22") (pintype "bidirectional"))
    )
    (net (code "109") (name "/N$LEDB83") (class "Default")
      (node (ref "83") (pin "2") (pinfunction "BLUE_2") (pintype "bidirectional"))
      (node (ref "IC6") (pin "32") (pinfunction "OUTB11_32") (pintype "bidirectional"))
    )
    (net (code "110") (name "/N$LEDB84") (class "Default")
      (node (ref "84") (pin "2") (pinfunction "BLUE_2") (pintype "bidirectional"))
      (node (ref "IC6") (pin "35") (pinfunction "OUTB15_35") (pintype "bidirectional"))
    )
    (net (code "111") (name "/N$LEDB85") (class "Default")
      (node (ref "85") (pin "2") (pinfunction "BLUE_2") (pintype "bidirectional"))
      (node (ref "IC6") (pin "19") (pinfunction "OUTB6_19") (pintype "bidirectional"))
    )
    (net (code "112") (name "/N$LEDB86") (class "Default")
      (node (ref "86") (pin "2") (pinfunction "BLUE_2") (pintype "bidirectional"))
      (node (ref "IC6") (pin "16") (pinfunction "OUTB2_16") (pintype "bidirectional"))
    )
    (net (code "113") (name "/N$LEDB87") (class "Default")
      (node (ref "87") (pin "2") (pinfunction "BLUE_2") (pintype "bidirectional"))
      (node (ref "IC6") (pin "38") (pinfunction "OUTB10_38") (pintype "bidirectional"))
    )
    (net (code "114") (name "/N$LEDB88") (class "Default")
      (node (ref "88") (pin "2") (pinfunction "BLUE_2") (pintype "bidirectional"))
      (node (ref "IC6") (pin "41") (pinfunction "OUTB14_41") (pintype "bidirectional"))
    )
    (net (code "115") (name "/N$LEDB89") (class "Default")
      (node (ref "89") (pin "2") (pinfunction "BLUE_2") (pintype "bidirectional"))
      (node (ref "IC6") (pin "13") (pinfunction "OUTB1_13") (pintype "bidirectional"))
    )
    (net (code "116") (name "/N$LEDB90") (class "Default")
      (node (ref "90") (pin "2") (pinfunction "BLUE_2") (pintype "bidirectional"))
      (node (ref "IC6") (pin "10") (pinfunction "OUTB5_10") (pintype "bidirectional"))
    )
    (net (code "117") (name "/N$LEDB91") (class "Default")
      (node (ref "91") (pin "2") (pinfunction "BLUE_2") (pintype "bidirectional"))
      (node (ref "IC6") (pin "44") (pinfunction "OUTB13_44") (pintype "bidirectional"))
    )
    (net (code "118") (name "/N$LEDB92") (class "Default")
      (node (ref "92") (pin "2") (pinfunction "BLUE_2") (pintype "bidirectional"))
      (node (ref "IC6") (pin "47") (pinfunction "OUTB9_47") (pintype "bidirectional"))
    )
    (net (code "119") (name "/N$LEDB93") (class "Default")
      (node (ref "93") (pin "2") (pinfunction "BLUE_2") (pintype "bidirectional"))
      (node (ref "IC6") (pin "4") (pinfunction "OUTB4_4") (pintype "bidirectional"))
    )
    (net (code "120") (name "/N$LEDB94") (class "Default")
      (node (ref "94") (pin "2") (pinfunction "BLUE_2") (pintype "bidirectional"))
      (node (ref "IC6") (pin "7") (pinfunction "OUTB0_7") (pintype "bidirectional"))
    )
    (net (code "121") (name "/N$LEDB95") (class "Default")
      (node (ref "95") (pin "2") (pinfunction "BLUE_2") (pintype "bidirectional"))
      (node (ref "IC6") (pin "50") (pinfunction "OUTB12_50") (pintype "bidirectional"))
    )
    (net (code "122") (name "/N$LEDB96") (class "Default")
      (node (ref "96") (pin "2") (pinfunction "BLUE_2") (pintype "bidirectional"))
      (node (ref "IC6") (pin "53") (pinfunction "OUTB8_53") (pintype "bidirectional"))
    )
    (net (code "123") (name "/N$LEDB97") (class "Default")
      (node (ref "97") (pin "2") (pinfunction "BLUE_2") (pintype "bidirectional"))
      (node (ref "IC7") (pin "25") (pinfunction "OUTB7_25") (pintype "bidirectional"))
    )
    (net (code "124") (name "/N$LEDB98") (class "Default")
      (node (ref "98") (pin "2") (pinfunction "BLUE_2") (pintype "bidirectional"))
      (node (ref "IC7") (pin "22") (pinfunction "OUTB3_22") (pintype "bidirectional"))
    )
    (net (code "125") (name "/N$LEDB99") (class "Default")
      (node (ref "99") (pin "2") (pinfunction "BLUE_2") (pintype "bidirectional"))
      (node (ref "IC7") (pin "32") (pinfunction "OUTB11_32") (pintype "bidirectional"))
    )
    (net (code "126") (name "/N$LEDB100") (class "Default")
      (node (ref "100") (pin "2") (pinfunction "BLUE_2") (pintype "bidirectional"))
      (node (ref "IC7") (pin "35") (pinfunction "OUTB15_35") (pintype "bidirectional"))
    )
    (net (code "127") (name "/N$LEDB101") (class "Default")
      (node (ref "101") (pin "2") (pinfunction "BLUE_2") (pintype "bidirectional"))
      (node (ref "IC7") (pin "19") (pinfunction "OUTB6_19") (pintype "bidirectional"))
    )
    (net (code "128") (name "/N$LEDB102") (class "Default")
      (node (ref "102") (pin "2") (pinfunction "BLUE_2") (pintype "bidirectional"))
      (node (ref "IC7") (pin "16") (pinfunction "OUTB2_16") (pintype "bidirectional"))
    )
    (net (code "129") (name "/N$LEDB103") (class "Default")
      (node (ref "103") (pin "2") (pinfunction "BLUE_2") (pintype "bidirectional"))
      (node (ref "IC7") (pin "38") (pinfunction "OUTB10_38") (pintype "bidirectional"))
    )
    (net (code "130") (name "/N$LEDB104") (class "Default")
      (node (ref "104") (pin "2") (pinfunction "BLUE_2") (pintype "bidirectional"))
      (node (ref "IC7") (pin "41") (pinfunction "OUTB14_41") (pintype "bidirectional"))
    )
    (net (code "131") (name "/N$LEDB105") (class "Default")
      (node (ref "105") (pin "2") (pinfunction "BLUE_2") (pintype "bidirectional"))
      (node (ref "IC7") (pin "13") (pinfunction "OUTB1_13") (pintype "bidirectional"))
    )
    (net (code "132") (name "/N$LEDB106") (class "Default")
      (node (ref "106") (pin "2") (pinfunction "BLUE_2") (pintype "bidirectional"))
      (node (ref "IC7") (pin "10") (pinfunction "OUTB5_10") (pintype "bidirectional"))
    )
    (net (code "133") (name "/N$LEDB107") (class "Default")
      (node (ref "107") (pin "2") (pinfunction "BLUE_2") (pintype "bidirectional"))
      (node (ref "IC7") (pin "44") (pinfunction "OUTB13_44") (pintype "bidirectional"))
    )
    (net (code "134") (name "/N$LEDB108") (class "Default")
      (node (ref "108") (pin "2") (pinfunction "BLUE_2") (pintype "bidirectional"))
      (node (ref "IC7") (pin "47") (pinfunction "OUTB9_47") (pintype "bidirectional"))
    )
    (net (code "135") (name "/N$LEDB109") (class "Default")
      (node (ref "109") (pin "2") (pinfunction "BLUE_2") (pintype "bidirectional"))
      (node (ref "IC7") (pin "4") (pinfunction "OUTB4_4") (pintype "bidirectional"))
    )
    (net (code "136") (name "/N$LEDB110") (class "Default")
      (node (ref "110") (pin "2") (pinfunction "BLUE_2") (pintype "bidirectional"))
      (node (ref "IC7") (pin "7") (pinfunction "OUTB0_7") (pintype "bidirectional"))
    )
    (net (code "137") (name "/N$LEDB111") (class "Default")
      (node (ref "111") (pin "2") (pinfunction "BLUE_2") (pintype "bidirectional"))
      (node (ref "IC7") (pin "50") (pinfunction "OUTB12_50") (pintype "bidirectional"))
    )
    (net (code "138") (name "/N$LEDB112") (class "Default")
      (node (ref "112") (pin "2") (pinfunction "BLUE_2") (pintype "bidirectional"))
      (node (ref "IC7") (pin "53") (pinfunction "OUTB8_53") (pintype "bidirectional"))
    )
    (net (code "139") (name "/N$LEDB113") (class "Default")
      (node (ref "113") (pin "2") (pinfunction "BLUE_2") (pintype "bidirectional"))
      (node (ref "IC8") (pin "25") (pinfunction "OUTB7_25") (pintype "bidirectional"))
    )
    (net (code "140") (name "/N$LEDB114") (class "Default")
      (node (ref "114") (pin "2") (pinfunction "BLUE_2") (pintype "bidirectional"))
      (node (ref "IC8") (pin "22") (pinfunction "OUTB3_22") (pintype "bidirectional"))
    )
    (net (code "141") (name "/N$LEDB115") (class "Default")
      (node (ref "115") (pin "2") (pinfunction "BLUE_2") (pintype "bidirectional"))
      (node (ref "IC8") (pin "32") (pinfunction "OUTB11_32") (pintype "bidirectional"))
    )
    (net (code "142") (name "/N$LEDB116") (class "Default")
      (node (ref "116") (pin "2") (pinfunction "BLUE_2") (pintype "bidirectional"))
      (node (ref "IC8") (pin "35") (pinfunction "OUTB15_35") (pintype "bidirectional"))
    )
    (net (code "143") (name "/N$LEDB117") (class "Default")
      (node (ref "117") (pin "2") (pinfunction "BLUE_2") (pintype "bidirectional"))
      (node (ref "IC8") (pin "19") (pinfunction "OUTB6_19") (pintype "bidirectional"))
    )
    (net (code "144") (name "/N$LEDB118") (class "Default")
      (node (ref "118") (pin "2") (pinfunction "BLUE_2") (pintype "bidirectional"))
      (node (ref "IC8") (pin "16") (pinfunction "OUTB2_16") (pintype "bidirectional"))
    )
    (net (code "145") (name "/N$LEDB119") (class "Default")
      (node (ref "119") (pin "2") (pinfunction "BLUE_2") (pintype "bidirectional"))
      (node (ref "IC8") (pin "38") (pinfunction "OUTB10_38") (pintype "bidirectional"))
    )
    (net (code "146") (name "/N$LEDB120") (class "Default")
      (node (ref "120") (pin "2") (pinfunction "BLUE_2") (pintype "bidirectional"))
      (node (ref "IC8") (pin "41") (pinfunction "OUTB14_41") (pintype "bidirectional"))
    )
    (net (code "147") (name "/N$LEDG1") (class "Default")
      (node (ref "1") (pin "1") (pinfunction "GREEN_1") (pintype "bidirectional"))
      (node (ref "IC1") (pin "27") (pinfunction "OUTG7_27") (pintype "bidirectional"))
    )
    (net (code "148") (name "/N$LEDG2") (class "Default")
      (node (ref "2") (pin "1") (pinfunction "GREEN_1") (pintype "bidirectional"))
      (node (ref "IC1") (pin "24") (pinfunction "OUTG3_24") (pintype "bidirectional"))
    )
    (net (code "149") (name "/N$LEDG3") (class "Default")
      (node (ref "3") (pin "1") (pinfunction "GREEN_1") (pintype "bidirectional"))
      (node (ref "IC1") (pin "30") (pinfunction "OUTG11_30") (pintype "bidirectional"))
    )
    (net (code "150") (name "/N$LEDG4") (class "Default")
      (node (ref "4") (pin "1") (pinfunction "GREEN_1") (pintype "bidirectional"))
      (node (ref "IC1") (pin "33") (pinfunction "OUTG15_33") (pintype "bidirectional"))
    )
    (net (code "151") (name "/N$LEDG5") (class "Default")
      (node (ref "5") (pin "1") (pinfunction "GREEN_1") (pintype "bidirectional"))
      (node (ref "IC1") (pin "21") (pinfunction "OUTG6_21") (pintype "bidirectional"))
    )
    (net (code "152") (name "/N$LEDG6") (class "Default")
      (node (ref "6") (pin "1") (pinfunction "GREEN_1") (pintype "bidirectional"))
      (node (ref "IC1") (pin "18") (pinfunction "OUTG2_18") (pintype "bidirectional"))
    )
    (net (code "153") (name "/N$LEDG7") (class "Default")
      (node (ref "7") (pin "1") (pinfunction "GREEN_1") (pintype "bidirectional"))
      (node (ref "IC1") (pin "36") (pinfunction "OUTG10_36") (pintype "bidirectional"))
    )
    (net (code "154") (name "/N$LEDG8") (class "Default")
      (node (ref "8") (pin "1") (pinfunction "GREEN_1") (pintype "bidirectional"))
      (node (ref "IC1") (pin "39") (pinfunction "OUTG14_39") (pintype "bidirectional"))
    )
    (net (code "155") (name "/N$LEDG9") (class "Default")
      (node (ref "9") (pin "1") (pinfunction "GREEN_1") (pintype "bidirectional"))
      (node (ref "IC1") (pin "15") (pinfunction "OUTG1_15") (pintype "bidirectional"))
    )
    (net (code "156") (name "/N$LEDG10") (class "Default")
      (node (ref "10") (pin "1") (pinfunction "GREEN_1") (pintype "bidirectional"))
      (node (ref "IC1") (pin "12") (pinfunction "OUTG5_12") (pintype "bidirectional"))
    )
    (net (code "157") (name "/N$LEDG11") (class "Default")
      (node (ref "11") (pin "1") (pinfunction "GREEN_1") (pintype "bidirectional"))
      (node (ref "IC1") (pin "42") (pinfunction "OUTG13_42") (pintype "bidirectional"))
    )
    (net (code "158") (name "/N$LEDG12") (class "Default")
      (node (ref "12") (pin "1") (pinfunction "GREEN_1") (pintype "bidirectional"))
      (node (ref "IC1") (pin "45") (pinfunction "OUTG9_45") (pintype "bidirectional"))
    )
    (net (code "159") (name "/N$LEDG13") (class "Default")
      (node (ref "13") (pin "1") (pinfunction "GREEN_1") (pintype "bidirectional"))
      (node (ref "IC1") (pin "6") (pinfunction "OUTG4_6") (pintype "bidirectional"))
    )
    (net (code "160") (name "/N$LEDG14") (class "Default")
      (node (ref "14") (pin "1") (pinfunction "GREEN_1") (pintype "bidirectional"))
      (node (ref "IC1") (pin "9") (pinfunction "OUTG0_9") (pintype "bidirectional"))
    )
    (net (code "161") (name "/N$LEDG15") (class "Default")
      (node (ref "15") (pin "1") (pinfunction "GREEN_1") (pintype "bidirectional"))
      (node (ref "IC1") (pin "48") (pinfunction "OUTG12_48") (pintype "bidirectional"))
    )
    (net (code "162") (name "/N$LEDG16") (class "Default")
      (node (ref "16") (pin "1") (pinfunction "GREEN_1") (pintype "bidirectional"))
      (node (ref "IC1") (pin "51") (pinfunction "OUTG8_51") (pintype "bidirectional"))
    )
    (net (code "163") (name "/N$LEDG17") (class "Default")
      (node (ref "17") (pin "1") (pinfunction "GREEN_1") (pintype "bidirectional"))
      (node (ref "IC2") (pin "27") (pinfunction "OUTG7_27") (pintype "bidirectional"))
    )
    (net (code "164") (name "/N$LEDG18") (class "Default")
      (node (ref "18") (pin "1") (pinfunction "GREEN_1") (pintype "bidirectional"))
      (node (ref "IC2") (pin "24") (pinfunction "OUTG3_24") (pintype "bidirectional"))
    )
    (net (code "165") (name "/N$LEDG19") (class "Default")
      (node (ref "19") (pin "1") (pinfunction "GREEN_1") (pintype "bidirectional"))
      (node (ref "IC2") (pin "30") (pinfunction "OUTG11_30") (pintype "bidirectional"))
    )
    (net (code "166") (name "/N$LEDG20") (class "Default")
      (node (ref "20") (pin "1") (pinfunction "GREEN_1") (pintype "bidirectional"))
      (node (ref "IC2") (pin "33") (pinfunction "OUTG15_33") (pintype "bidirectional"))
    )
    (net (code "167") (name "/N$LEDG21") (class "Default")
      (node (ref "21") (pin "1") (pinfunction "GREEN_1") (pintype "bidirectional"))
      (node (ref "IC2") (pin "21") (pinfunction "OUTG6_21") (pintype "bidirectional"))
    )
    (net (code "168") (name "/N$LEDG22") (class "Default")
      (node (ref "22") (pin "1") (pinfunction "GREEN_1") (pintype "bidirectional"))
      (node (ref "IC2") (pin "18") (pinfunction "OUTG2_18") (pintype "bidirectional"))
    )
    (net (code "169") (name "/N$LEDG23") (class "Default")
      (node (ref "23") (pin "1") (pinfunction "GREEN_1") (pintype "bidirectional"))
      (node (ref "IC2") (pin "36") (pinfunction "OUTG10_36") (pintype "bidirectional"))
    )
    (net (code "170") (name "/N$LEDG24") (class "Default")
      (node (ref "24") (pin "1") (pinfunction "GREEN_1") (pintype "bidirectional"))
      (node (ref "IC2") (pin "39") (pinfunction "OUTG14_39") (pintype "bidirectional"))
    )
    (net (code "171") (name "/N$LEDG25") (class "Default")
      (node (ref "25") (pin "1") (pinfunction "GREEN_1") (pintype "bidirectional"))
      (node (ref "IC2") (pin "15") (pinfunction "OUTG1_15") (pintype "bidirectional"))
    )
    (net (code "172") (name "/N$LEDG26") (class "Default")
      (node (ref "26") (pin "1") (pinfunction "GREEN_1") (pintype "bidirectional"))
      (node (ref "IC2") (pin "12") (pinfunction "OUTG5_12") (pintype "bidirectional"))
    )
    (net (code "173") (name "/N$LEDG27") (class "Default")
      (node (ref "27") (pin "1") (pinfunction "GREEN_1") (pintype "bidirectional"))
      (node (ref "IC2") (pin "42") (pinfunction "OUTG13_42") (pintype "bidirectional"))
    )
    (net (code "174") (name "/N$LEDG28") (class "Default")
      (node (ref "28") (pin "1") (pinfunction "GREEN_1") (pintype "bidirectional"))
      (node (ref "IC2") (pin "45") (pinfunction "OUTG9_45") (pintype "bidirectional"))
    )
    (net (code "175") (name "/N$LEDG29") (class "Default")
      (node (ref "29") (pin "1") (pinfunction "GREEN_1") (pintype "bidirectional"))
      (node (ref "IC2") (pin "6") (pinfunction "OUTG4_6") (pintype "bidirectional"))
    )
    (net (code "176") (name "/N$LEDG30") (class "Default")
      (node (ref "30") (pin "1") (pinfunction "GREEN_1") (pintype "bidirectional"))
      (node (ref "IC2") (pin "9") (pinfunction "OUTG0_9") (pintype "bidirectional"))
    )
    (net (code "177") (name "/N$LEDG31") (class "Default")
      (node (ref "31") (pin "1") (pinfunction "GREEN_1") (pintype "bidirectional"))
      (node (ref "IC2") (pin "48") (pinfunction "OUTG12_48") (pintype "bidirectional"))
    )
    (net (code "178") (name "/N$LEDG32") (class "Default")
      (node (ref "32") (pin "1") (pinfunction "GREEN_1") (pintype "bidirectional"))
      (node (ref "IC2") (pin "51") (pinfunction "OUTG8_51") (pintype "bidirectional"))
    )
    (net (code "179") (name "/N$LEDG33") (class "Default")
      (node (ref "33") (pin "1") (pinfunction "GREEN_1") (pintype "bidirectional"))
      (node (ref "IC3") (pin "27") (pinfunction "OUTG7_27") (pintype "bidirectional"))
    )
    (net (code "180") (name "/N$LEDG34") (class "Default")
      (node (ref "34") (pin "1") (pinfunction "GREEN_1") (pintype "bidirectional"))
      (node (ref "IC3") (pin "24") (pinfunction "OUTG3_24") (pintype "bidirectional"))
    )
    (net (code "181") (name "/N$LEDG35") (class "Default")
      (node (ref "35") (pin "1") (pinfunction "GREEN_1") (pintype "bidirectional"))
      (node (ref "IC3") (pin "30") (pinfunction "OUTG11_30") (pintype "bidirectional"))
    )
    (net (code "182") (name "/N$LEDG36") (class "Default")
      (node (ref "36") (pin "1") (pinfunction "GREEN_1") (pintype "bidirectional"))
      (node (ref "IC3") (pin "33") (pinfunction "OUTG15_33") (pintype "bidirectional"))
    )
    (net (code "183") (name "/N$LEDG37") (class "Default")
      (node (ref "37") (pin "1") (pinfunction "GREEN_1") (pintype "bidirectional"))
      (node (ref "IC3") (pin "21") (pinfunction "OUTG6_21") (pintype "bidirectional"))
    )
    (net (code "184") (name "/N$LEDG38") (class "Default")
      (node (ref "38") (pin "1") (pinfunction "GREEN_1") (pintype "bidirectional"))
      (node (ref "IC3") (pin "18") (pinfunction "OUTG2_18") (pintype "bidirectional"))
    )
    (net (code "185") (name "/N$LEDG39") (class "Default")
      (node (ref "39") (pin "1") (pinfunction "GREEN_1") (pintype "bidirectional"))
      (node (ref "IC3") (pin "36") (pinfunction "OUTG10_36") (pintype "bidirectional"))
    )
    (net (code "186") (name "/N$LEDG40") (class "Default")
      (node (ref "40") (pin "1") (pinfunction "GREEN_1") (pintype "bidirectional"))
      (node (ref "IC3") (pin "39") (pinfunction "OUTG14_39") (pintype "bidirectional"))
    )
    (net (code "187") (name "/N$LEDG41") (class "Default")
      (node (ref "41") (pin "1") (pinfunction "GREEN_1") (pintype "bidirectional"))
      (node (ref "IC3") (pin "15") (pinfunction "OUTG1_15") (pintype "bidirectional"))
    )
    (net (code "188") (name "/N$LEDG42") (class "Default")
      (node (ref "42") (pin "1") (pinfunction "GREEN_1") (pintype "bidirectional"))
      (node (ref "IC3") (pin "12") (pinfunction "OUTG5_12") (pintype "bidirectional"))
    )
    (net (code "189") (name "/N$LEDG43") (class "Default")
      (node (ref "43") (pin "1") (pinfunction "GREEN_1") (pintype "bidirectional"))
      (node (ref "IC3") (pin "42") (pinfunction "OUTG13_42") (pintype "bidirectional"))
    )
    (net (code "190") (name "/N$LEDG44") (class "Default")
      (node (ref "44") (pin "1") (pinfunction "GREEN_1") (pintype "bidirectional"))
      (node (ref "IC3") (pin "45") (pinfunction "OUTG9_45") (pintype "bidirectional"))
    )
    (net (code "191") (name "/N$LEDG45") (class "Default")
      (node (ref "45") (pin "1") (pinfunction "GREEN_1") (pintype "bidirectional"))
      (node (ref "IC3") (pin "6") (pinfunction "OUTG4_6") (pintype "bidirectional"))
    )
    (net (code "192") (name "/N$LEDG46") (class "Default")
      (node (ref "46") (pin "1") (pinfunction "GREEN_1") (pintype "bidirectional"))
      (node (ref "IC3") (pin "9") (pinfunction "OUTG0_9") (pintype "bidirectional"))
    )
    (net (code "193") (name "/N$LEDG47") (class "Default")
      (node (ref "47") (pin "1") (pinfunction "GREEN_1") (pintype "bidirectional"))
      (node (ref "IC3") (pin "48") (pinfunction "OUTG12_48") (pintype "bidirectional"))
    )
    (net (code "194") (name "/N$LEDG48") (class "Default")
      (node (ref "48") (pin "1") (pinfunction "GREEN_1") (pintype "bidirectional"))
      (node (ref "IC3") (pin "51") (pinfunction "OUTG8_51") (pintype "bidirectional"))
    )
    (net (code "195") (name "/N$LEDG49") (class "Default")
      (node (ref "49") (pin "1") (pinfunction "GREEN_1") (pintype "bidirectional"))
      (node (ref "IC4") (pin "27") (pinfunction "OUTG7_27") (pintype "bidirectional"))
    )
    (net (code "196") (name "/N$LEDG50") (class "Default")
      (node (ref "50") (pin "1") (pinfunction "GREEN_1") (pintype "bidirectional"))
      (node (ref "IC4") (pin "24") (pinfunction "OUTG3_24") (pintype "bidirectional"))
    )
    (net (code "197") (name "/N$LEDG51") (class "Default")
      (node (ref "51") (pin "1") (pinfunction "GREEN_1") (pintype "bidirectional"))
      (node (ref "IC4") (pin "30") (pinfunction "OUTG11_30") (pintype "bidirectional"))
    )
    (net (code "198") (name "/N$LEDG52") (class "Default")
      (node (ref "52") (pin "1") (pinfunction "GREEN_1") (pintype "bidirectional"))
      (node (ref "IC4") (pin "33") (pinfunction "OUTG15_33") (pintype "bidirectional"))
    )
    (net (code "199") (name "/N$LEDG53") (class "Default")
      (node (ref "53") (pin "1") (pinfunction "GREEN_1") (pintype "bidirectional"))
      (node (ref "IC4") (pin "21") (pinfunction "OUTG6_21") (pintype "bidirectional"))
    )
    (net (code "200") (name "/N$LEDG54") (class "Default")
      (node (ref "54") (pin "1") (pinfunction "GREEN_1") (pintype "bidirectional"))
      (node (ref "IC4") (pin "18") (pinfunction "OUTG2_18") (pintype "bidirectional"))
    )
    (net (code "201") (name "/N$LEDG55") (class "Default")
      (node (ref "55") (pin "1") (pinfunction "GREEN_1") (pintype "bidirectional"))
      (node (ref "IC4") (pin "36") (pinfunction "OUTG10_36") (pintype "bidirectional"))
    )
    (net (code "202") (name "/N$LEDG56") (class "Default")
      (node (ref "56") (pin "1") (pinfunction "GREEN_1") (pintype "bidirectional"))
      (node (ref "IC4") (pin "39") (pinfunction "OUTG14_39") (pintype "bidirectional"))
    )
    (net (code "203") (name "/N$LEDG57") (class "Default")
      (node (ref "57") (pin "1") (pinfunction "GREEN_1") (pintype "bidirectional"))
      (node (ref "IC4") (pin "15") (pinfunction "OUTG1_15") (pintype "bidirectional"))
    )
    (net (code "204") (name "/N$LEDG58") (class "Default")
      (node (ref "58") (pin "1") (pinfunction "GREEN_1") (pintype "bidirectional"))
      (node (ref "IC4") (pin "12") (pinfunction "OUTG5_12") (pintype "bidirectional"))
    )
    (net (code "205") (name "/N$LEDG59") (class "Default")
      (node (ref "59") (pin "1") (pinfunction "GREEN_1") (pintype "bidirectional"))
      (node (ref "IC4") (pin "42") (pinfunction "OUTG13_42") (pintype "bidirectional"))
    )
    (net (code "206") (name "/N$LEDG60") (class "Default")
      (node (ref "60") (pin "1") (pinfunction "GREEN_1") (pintype "bidirectional"))
      (node (ref "IC4") (pin "45") (pinfunction "OUTG9_45") (pintype "bidirectional"))
    )
    (net (code "207") (name "/N$LEDG61") (class "Default")
      (node (ref "61") (pin "1") (pinfunction "GREEN_1") (pintype "bidirectional"))
      (node (ref "IC4") (pin "6") (pinfunction "OUTG4_6") (pintype "bidirectional"))
    )
    (net (code "208") (name "/N$LEDG62") (class "Default")
      (node (ref "62") (pin "1") (pinfunction "GREEN_1") (pintype "bidirectional"))
      (node (ref "IC4") (pin "9") (pinfunction "OUTG0_9") (pintype "bidirectional"))
    )
    (net (code "209") (name "/N$LEDG63") (class "Default")
      (node (ref "63") (pin "1") (pinfunction "GREEN_1") (pintype "bidirectional"))
      (node (ref "IC4") (pin "48") (pinfunction "OUTG12_48") (pintype "bidirectional"))
    )
    (net (code "210") (name "/N$LEDG64") (class "Default")
      (node (ref "64") (pin "1") (pinfunction "GREEN_1") (pintype "bidirectional"))
      (node (ref "IC4") (pin "51") (pinfunction "OUTG8_51") (pintype "bidirectional"))
    )
    (net (code "211") (name "/N$LEDG65") (class "Default")
      (node (ref "65") (pin "1") (pinfunction "GREEN_1") (pintype "bidirectional"))
      (node (ref "IC5") (pin "27") (pinfunction "OUTG7_27") (pintype "bidirectional"))
    )
    (net (code "212") (name "/N$LEDG66") (class "Default")
      (node (ref "66") (pin "1") (pinfunction "GREEN_1") (pintype "bidirectional"))
      (node (ref "IC5") (pin "24") (pinfunction "OUTG3_24") (pintype "bidirectional"))
    )
    (net (code "213") (name "/N$LEDG67") (class "Default")
      (node (ref "67") (pin "1") (pinfunction "GREEN_1") (pintype "bidirectional"))
      (node (ref "IC5") (pin "30") (pinfunction "OUTG11_30") (pintype "bidirectional"))
    )
    (net (code "214") (name "/N$LEDG68") (class "Default")
      (node (ref "68") (pin "1") (pinfunction "GREEN_1") (pintype "bidirectional"))
      (node (ref "IC5") (pin "33") (pinfunction "OUTG15_33") (pintype "bidirectional"))
    )
    (net (code "215") (name "/N$LEDG69") (class "Default")
      (node (ref "69") (pin "1") (pinfunction "GREEN_1") (pintype "bidirectional"))
      (node (ref "IC5") (pin "21") (pinfunction "OUTG6_21") (pintype "bidirectional"))
    )
    (net (code "216") (name "/N$LEDG70") (class "Default")
      (node (ref "70") (pin "1") (pinfunction "GREEN_1") (pintype "bidirectional"))
      (node (ref "IC5") (pin "18") (pinfunction "OUTG2_18") (pintype "bidirectional"))
    )
    (net (code "217") (name "/N$LEDG71") (class "Default")
      (node (ref "71") (pin "1") (pinfunction "GREEN_1") (pintype "bidirectional"))
      (node (ref "IC5") (pin "36") (pinfunction "OUTG10_36") (pintype "bidirectional"))
    )
    (net (code "218") (name "/N$LEDG72") (class "Default")
      (node (ref "72") (pin "1") (pinfunction "GREEN_1") (pintype "bidirectional"))
      (node (ref "IC5") (pin "39") (pinfunction "OUTG14_39") (pintype "bidirectional"))
    )
    (net (code "219") (name "/N$LEDG73") (class "Default")
      (node (ref "73") (pin "1") (pinfunction "GREEN_1") (pintype "bidirectional"))
      (node (ref "IC5") (pin "15") (pinfunction "OUTG1_15") (pintype "bidirectional"))
    )
    (net (code "220") (name "/N$LEDG74") (class "Default")
      (node (ref "74") (pin "1") (pinfunction "GREEN_1") (pintype "bidirectional"))
      (node (ref "IC5") (pin "12") (pinfunction "OUTG5_12") (pintype "bidirectional"))
    )
    (net (code "221") (name "/N$LEDG75") (class "Default")
      (node (ref "75") (pin "1") (pinfunction "GREEN_1") (pintype "bidirectional"))
      (node (ref "IC5") (pin "42") (pinfunction "OUTG13_42") (pintype "bidirectional"))
    )
    (net (code "222") (name "/N$LEDG76") (class "Default")
      (node (ref "76") (pin "1") (pinfunction "GREEN_1") (pintype "bidirectional"))
      (node (ref "IC5") (pin "45") (pinfunction "OUTG9_45") (pintype "bidirectional"))
    )
    (net (code "223") (name "/N$LEDG77") (class "Default")
      (node (ref "77") (pin "1") (pinfunction "GREEN_1") (pintype "bidirectional"))
      (node (ref "IC5") (pin "6") (pinfunction "OUTG4_6") (pintype "bidirectional"))
    )
    (net (code "224") (name "/N$LEDG78") (class "Default")
      (node (ref "78") (pin "1") (pinfunction "GREEN_1") (pintype "bidirectional"))
      (node (ref "IC5") (pin "9") (pinfunction "OUTG0_9") (pintype "bidirectional"))
    )
    (net (code "225") (name "/N$LEDG79") (class "Default")
      (node (ref "79") (pin "1") (pinfunction "GREEN_1") (pintype "bidirectional"))
      (node (ref "IC5") (pin "48") (pinfunction "OUTG12_48") (pintype "bidirectional"))
    )
    (net (code "226") (name "/N$LEDG80") (class "Default")
      (node (ref "80") (pin "1") (pinfunction "GREEN_1") (pintype "bidirectional"))
      (node (ref "IC5") (pin "51") (pinfunction "OUTG8_51") (pintype "bidirectional"))
    )
    (net (code "227") (name "/N$LEDG81") (class "Default")
      (node (ref "81") (pin "1") (pinfunction "GREEN_1") (pintype "bidirectional"))
      (node (ref "IC6") (pin "27") (pinfunction "OUTG7_27") (pintype "bidirectional"))
    )
    (net (code "228") (name "/N$LEDG82") (class "Default")
      (node (ref "82") (pin "1") (pinfunction "GREEN_1") (pintype "bidirectional"))
      (node (ref "IC6") (pin "24") (pinfunction "OUTG3_24") (pintype "bidirectional"))
    )
    (net (code "229") (name "/N$LEDG83") (class "Default")
      (node (ref "83") (pin "1") (pinfunction "GREEN_1") (pintype "bidirectional"))
      (node (ref "IC6") (pin "30") (pinfunction "OUTG11_30") (pintype "bidirectional"))
    )
    (net (code "230") (name "/N$LEDG84") (class "Default")
      (node (ref "84") (pin "1") (pinfunction "GREEN_1") (pintype "bidirectional"))
      (node (ref "IC6") (pin "33") (pinfunction "OUTG15_33") (pintype "bidirectional"))
    )
    (net (code "231") (name "/N$LEDG85") (class "Default")
      (node (ref "85") (pin "1") (pinfunction "GREEN_1") (pintype "bidirectional"))
      (node (ref "IC6") (pin "21") (pinfunction "OUTG6_21") (pintype "bidirectional"))
    )
    (net (code "232") (name "/N$LEDG86") (class "Default")
      (node (ref "86") (pin "1") (pinfunction "GREEN_1") (pintype "bidirectional"))
      (node (ref "IC6") (pin "18") (pinfunction "OUTG2_18") (pintype "bidirectional"))
    )
    (net (code "233") (name "/N$LEDG87") (class "Default")
      (node (ref "87") (pin "1") (pinfunction "GREEN_1") (pintype "bidirectional"))
      (node (ref "IC6") (pin "36") (pinfunction "OUTG10_36") (pintype "bidirectional"))
    )
    (net (code "234") (name "/N$LEDG88") (class "Default")
      (node (ref "88") (pin "1") (pinfunction "GREEN_1") (pintype "bidirectional"))
      (node (ref "IC6") (pin "39") (pinfunction "OUTG14_39") (pintype "bidirectional"))
    )
    (net (code "235") (name "/N$LEDG89") (class "Default")
      (node (ref "89") (pin "1") (pinfunction "GREEN_1") (pintype "bidirectional"))
      (node (ref "IC6") (pin "15") (pinfunction "OUTG1_15") (pintype "bidirectional"))
    )
    (net (code "236") (name "/N$LEDG90") (class "Default")
      (node (ref "90") (pin "1") (pinfunction "GREEN_1") (pintype "bidirectional"))
      (node (ref "IC6") (pin "12") (pinfunction "OUTG5_12") (pintype "bidirectional"))
    )
    (net (code "237") (name "/N$LEDG91") (class "Default")
      (node (ref "91") (pin "1") (pinfunction "GREEN_1") (pintype "bidirectional"))
      (node (ref "IC6") (pin "42") (pinfunction "OUTG13_42") (pintype "bidirectional"))
    )
    (net (code "238") (name "/N$LEDG92") (class "Default")
      (node (ref "92") (pin "1") (pinfunction "GREEN_1") (pintype "bidirectional"))
      (node (ref "IC6") (pin "45") (pinfunction "OUTG9_45") (pintype "bidirectional"))
    )
    (net (code "239") (name "/N$LEDG93") (class "Default")
      (node (ref "93") (pin "1") (pinfunction "GREEN_1") (pintype "bidirectional"))
      (node (ref "IC6") (pin "6") (pinfunction "OUTG4_6") (pintype "bidirectional"))
    )
    (net (code "240") (name "/N$LEDG94") (class "Default")
      (node (ref "94") (pin "1") (pinfunction "GREEN_1") (pintype "bidirectional"))
      (node (ref "IC6") (pin "9") (pinfunction "OUTG0_9") (pintype "bidirectional"))
    )
    (net (code "241") (name "/N$LEDG95") (class "Default")
      (node (ref "95") (pin "1") (pinfunction "GREEN_1") (pintype "bidirectional"))
      (node (ref "IC6") (pin "48") (pinfunction "OUTG12_48") (pintype "bidirectional"))
    )
    (net (code "242") (name "/N$LEDG96") (class "Default")
      (node (ref "96") (pin "1") (pinfunction "GREEN_1") (pintype "bidirectional"))
      (node (ref "IC6") (pin "51") (pinfunction "OUTG8_51") (pintype "bidirectional"))
    )
    (net (code "243") (name "/N$LEDG97") (class "Default")
      (node (ref "97") (pin "1") (pinfunction "GREEN_1") (pintype "bidirectional"))
      (node (ref "IC7") (pin "27") (pinfunction "OUTG7_27") (pintype "bidirectional"))
    )
    (net (code "244") (name "/N$LEDG98") (class "Default")
      (node (ref "98") (pin "1") (pinfunction "GREEN_1") (pintype "bidirectional"))
      (node (ref "IC7") (pin "24") (pinfunction "OUTG3_24") (pintype "bidirectional"))
    )
    (net (code "245") (name "/N$LEDG99") (class "Default")
      (node (ref "99") (pin "1") (pinfunction "GREEN_1") (pintype "bidirectional"))
      (node (ref "IC7") (pin "30") (pinfunction "OUTG11_30") (pintype "bidirectional"))
    )
    (net (code "246") (name "/N$LEDG100") (class "Default")
      (node (ref "100") (pin "1") (pinfunction "GREEN_1") (pintype "bidirectional"))
      (node (ref "IC7") (pin "33") (pinfunction "OUTG15_33") (pintype "bidirectional"))
    )
    (net (code "247") (name "/N$LEDG101") (class "Default")
      (node (ref "101") (pin "1") (pinfunction "GREEN_1") (pintype "bidirectional"))
      (node (ref "IC7") (pin "21") (pinfunction "OUTG6_21") (pintype "bidirectional"))
    )
    (net (code "248") (name "/N$LEDG102") (class "Default")
      (node (ref "102") (pin "1") (pinfunction "GREEN_1") (pintype "bidirectional"))
      (node (ref "IC7") (pin "18") (pinfunction "OUTG2_18") (pintype "bidirectional"))
    )
    (net (code "249") (name "/N$LEDG103") (class "Default")
      (node (ref "103") (pin "1") (pinfunction "GREEN_1") (pintype "bidirectional"))
      (node (ref "IC7") (pin "36") (pinfunction "OUTG10_36") (pintype "bidirectional"))
    )
    (net (code "250") (name "/N$LEDG104") (class "Default")
      (node (ref "104") (pin "1") (pinfunction "GREEN_1") (pintype "bidirectional"))
      (node (ref "IC7") (pin "39") (pinfunction "OUTG14_39") (pintype "bidirectional"))
    )
    (net (code "251") (name "/N$LEDG105") (class "Default")
      (node (ref "105") (pin "1") (pinfunction "GREEN_1") (pintype "bidirectional"))
      (node (ref "IC7") (pin "15") (pinfunction "OUTG1_15") (pintype "bidirectional"))
    )
    (net (code "252") (name "/N$LEDG106") (class "Default")
      (node (ref "106") (pin "1") (pinfunction "GREEN_1") (pintype "bidirectional"))
      (node (ref "IC7") (pin "12") (pinfunction "OUTG5_12") (pintype "bidirectional"))
    )
    (net (code "253") (name "/N$LEDG107") (class "Default")
      (node (ref "107") (pin "1") (pinfunction "GREEN_1") (pintype "bidirectional"))
      (node (ref "IC7") (pin "42") (pinfunction "OUTG13_42") (pintype "bidirectional"))
    )
    (net (code "254") (name "/N$LEDG108") (class "Default")
      (node (ref "108") (pin "1") (pinfunction "GREEN_1") (pintype "bidirectional"))
      (node (ref "IC7") (pin "45") (pinfunction "OUTG9_45") (pintype "bidirectional"))
    )
    (net (code "255") (name "/N$LEDG109") (class "Default")
      (node (ref "109") (pin "1") (pinfunction "GREEN_1") (pintype "bidirectional"))
      (node (ref "IC7") (pin "6") (pinfunction "OUTG4_6") (pintype "bidirectional"))
    )
    (net (code "256") (name "/N$LEDG110") (class "Default")
      (node (ref "110") (pin "1") (pinfunction "GREEN_1") (pintype "bidirectional"))
      (node (ref "IC7") (pin "9") (pinfunction "OUTG0_9") (pintype "bidirectional"))
    )
    (net (code "257") (name "/N$LEDG111") (class "Default")
      (node (ref "111") (pin "1") (pinfunction "GREEN_1") (pintype "bidirectional"))
      (node (ref "IC7") (pin "48") (pinfunction "OUTG12_48") (pintype "bidirectional"))
    )
    (net (code "258") (name "/N$LEDG112") (class "Default")
      (node (ref "112") (pin "1") (pinfunction "GREEN_1") (pintype "bidirectional"))
      (node (ref "IC7") (pin "51") (pinfunction "OUTG8_51") (pintype "bidirectional"))
    )
    (net (code "259") (name "/N$LEDG113") (class "Default")
      (node (ref "113") (pin "1") (pinfunction "GREEN_1") (pintype "bidirectional"))
      (node (ref "IC8") (pin "27") (pinfunction "OUTG7_27") (pintype "bidirectional"))
    )
    (net (code "260") (name "/N$LEDG114") (class "Default")
      (node (ref "114") (pin "1") (pinfunction "GREEN_1") (pintype "bidirectional"))
      (node (ref "IC8") (pin "24") (pinfunction "OUTG3_24") (pintype "bidirectional"))
    )
    (net (code "261") (name "/N$LEDG115") (class "Default")
      (node (ref "115") (pin "1") (pinfunction "GREEN_1") (pintype "bidirectional"))
      (node (ref "IC8") (pin "30") (pinfunction "OUTG11_30") (pintype "bidirectional"))
    )
    (net (code "262") (name "/N$LEDG116") (class "Default")
      (node (ref "116") (pin "1") (pinfunction "GREEN_1") (pintype "bidirectional"))
      (node (ref "IC8") (pin "33") (pinfunction "OUTG15_33") (pintype "bidirectional"))
    )
    (net (code "263") (name "/N$LEDG117") (class "Default")
      (node (ref "117") (pin "1") (pinfunction "GREEN_1") (pintype "bidirectional"))
      (node (ref "IC8") (pin "21") (pinfunction "OUTG6_21") (pintype "bidirectional"))
    )
    (net (code "264") (name "/N$LEDG118") (class "Default")
      (node (ref "118") (pin "1") (pinfunction "GREEN_1") (pintype "bidirectional"))
      (node (ref "IC8") (pin "18") (pinfunction "OUTG2_18") (pintype "bidirectional"))
    )
    (net (code "265") (name "/N$LEDG119") (class "Default")
      (node (ref "119") (pin "1") (pinfunction "GREEN_1") (pintype "bidirectional"))
      (node (ref "IC8") (pin "36") (pinfunction "OUTG10_36") (pintype "bidirectional"))
    )
    (net (code "266") (name "/N$LEDG120") (class "Default")
      (node (ref "120") (pin "1") (pinfunction "GREEN_1") (pintype "bidirectional"))
      (node (ref "IC8") (pin "39") (pinfunction "OUTG14_39") (pintype "bidirectional"))
    )
    (net (code "267") (name "/N$LEDR1") (class "Default")
      (node (ref "1") (pin "4") (pinfunction "RED_4") (pintype "bidirectional"))
      (node (ref "IC1") (pin "26") (pinfunction "OUTR7_26") (pintype "bidirectional"))
    )
    (net (code "268") (name "/N$LEDR2") (class "Default")
      (node (ref "2") (pin "4") (pinfunction "RED_4") (pintype "bidirectional"))
      (node (ref "IC1") (pin "23") (pinfunction "OUTR3_23") (pintype "bidirectional"))
    )
    (net (code "269") (name "/N$LEDR3") (class "Default")
      (node (ref "3") (pin "4") (pinfunction "RED_4") (pintype "bidirectional"))
      (node (ref "IC1") (pin "31") (pinfunction "OUTR11_31") (pintype "bidirectional"))
    )
    (net (code "270") (name "/N$LEDR4") (class "Default")
      (node (ref "4") (pin "4") (pinfunction "RED_4") (pintype "bidirectional"))
      (node (ref "IC1") (pin "34") (pinfunction "OUTR15_34") (pintype "bidirectional"))
    )
    (net (code "271") (name "/N$LEDR5") (class "Default")
      (node (ref "5") (pin "4") (pinfunction "RED_4") (pintype "bidirectional"))
      (node (ref "IC1") (pin "20") (pinfunction "OUTR6_20") (pintype "bidirectional"))
    )
    (net (code "272") (name "/N$LEDR6") (class "Default")
      (node (ref "6") (pin "4") (pinfunction "RED_4") (pintype "bidirectional"))
      (node (ref "IC1") (pin "17") (pinfunction "OUTR2_17") (pintype "bidirectional"))
    )
    (net (code "273") (name "/N$LEDR7") (class "Default")
      (node (ref "7") (pin "4") (pinfunction "RED_4") (pintype "bidirectional"))
      (node (ref "IC1") (pin "37") (pinfunction "OUTR10_37") (pintype "bidirectional"))
    )
    (net (code "274") (name "/N$LEDR8") (class "Default")
      (node (ref "8") (pin "4") (pinfunction "RED_4") (pintype "bidirectional"))
      (node (ref "IC1") (pin "40") (pinfunction "OUTR14_40") (pintype "bidirectional"))
    )
    (net (code "275") (name "/N$LEDR9") (class "Default")
      (node (ref "9") (pin "4") (pinfunction "RED_4") (pintype "bidirectional"))
      (node (ref "IC1") (pin "14") (pinfunction "OUTR1_14") (pintype "bidirectional"))
    )
    (net (code "276") (name "/N$LEDR10") (class "Default")
      (node (ref "10") (pin "4") (pinfunction "RED_4") (pintype "bidirectional"))
      (node (ref "IC1") (pin "11") (pinfunction "OUTR5_11") (pintype "bidirectional"))
    )
    (net (code "277") (name "/N$LEDR11") (class "Default")
      (node (ref "11") (pin "4") (pinfunction "RED_4") (pintype "bidirectional"))
      (node (ref "IC1") (pin "43") (pinfunction "OUTR13_43") (pintype "bidirectional"))
    )
    (net (code "278") (name "/N$LEDR12") (class "Default")
      (node (ref "12") (pin "4") (pinfunction "RED_4") (pintype "bidirectional"))
      (node (ref "IC1") (pin "46") (pinfunction "OUTR9_46") (pintype "bidirectional"))
    )
    (net (code "279") (name "/N$LEDR13") (class "Default")
      (node (ref "13") (pin "4") (pinfunction "RED_4") (pintype "bidirectional"))
      (node (ref "IC1") (pin "5") (pinfunction "OUTR4_5") (pintype "bidirectional"))
    )
    (net (code "280") (name "/N$LEDR14") (class "Default")
      (node (ref "14") (pin "4") (pinfunction "RED_4") (pintype "bidirectional"))
      (node (ref "IC1") (pin "8") (pinfunction "OUTR0_8") (pintype "bidirectional"))
    )
    (net (code "281") (name "/N$LEDR15") (class "Default")
      (node (ref "15") (pin "4") (pinfunction "RED_4") (pintype "bidirectional"))
      (node (ref "IC1") (pin "49") (pinfunction "OUTR12_49") (pintype "bidirectional"))
    )
    (net (code "282") (name "/N$LEDR16") (class "Default")
      (node (ref "16") (pin "4") (pinfunction "RED_4") (pintype "bidirectional"))
      (node (ref "IC1") (pin "52") (pinfunction "OUTR8_52") (pintype "bidirectional"))
    )
    (net (code "283") (name "/N$LEDR17") (class "Default")
      (node (ref "17") (pin "4") (pinfunction "RED_4") (pintype "bidirectional"))
      (node (ref "IC2") (pin "26") (pinfunction "OUTR7_26") (pintype "bidirectional"))
    )
    (net (code "284") (name "/N$LEDR18") (class "Default")
      (node (ref "18") (pin "4") (pinfunction "RED_4") (pintype "bidirectional"))
      (node (ref "IC2") (pin "23") (pinfunction "OUTR3_23") (pintype "bidirectional"))
    )
    (net (code "285") (name "/N$LEDR19") (class "Default")
      (node (ref "19") (pin "4") (pinfunction "RED_4") (pintype "bidirectional"))
      (node (ref "IC2") (pin "31") (pinfunction "OUTR11_31") (pintype "bidirectional"))
    )
    (net (code "286") (name "/N$LEDR20") (class "Default")
      (node (ref "20") (pin "4") (pinfunction "RED_4") (pintype "bidirectional"))
      (node (ref "IC2") (pin "34") (pinfunction "OUTR15_34") (pintype "bidirectional"))
    )
    (net (code "287") (name "/N$LEDR21") (class "Default")
      (node (ref "21") (pin "4") (pinfunction "RED_4") (pintype "bidirectional"))
      (node (ref "IC2") (pin "20") (pinfunction "OUTR6_20") (pintype "bidirectional"))
    )
    (net (code "288") (name "/N$LEDR22") (class "Default")
      (node (ref "22") (pin "4") (pinfunction "RED_4") (pintype "bidirectional"))
      (node (ref "IC2") (pin "17") (pinfunction "OUTR2_17") (pintype "bidirectional"))
    )
    (net (code "289") (name "/N$LEDR23") (class "Default")
      (node (ref "23") (pin "4") (pinfunction "RED_4") (pintype "bidirectional"))
      (node (ref "IC2") (pin "37") (pinfunction "OUTR10_37") (pintype "bidirectional"))
    )
    (net (code "290") (name "/N$LEDR24") (class "Default")
      (node (ref "24") (pin "4") (pinfunction "RED_4") (pintype "bidirectional"))
      (node (ref "IC2") (pin "40") (pinfunction "OUTR14_40") (pintype "bidirectional"))
    )
    (net (code "291") (name "/N$LEDR25") (class "Default")
      (node (ref "25") (pin "4") (pinfunction "RED_4") (pintype "bidirectional"))
      (node (ref "IC2") (pin "14") (pinfunction "OUTR1_14") (pintype "bidirectional"))
    )
    (net (code "292") (name "/N$LEDR26") (class "Default")
      (node (ref "26") (pin "4") (pinfunction "RED_4") (pintype "bidirectional"))
      (node (ref "IC2") (pin "11") (pinfunction "OUTR5_11") (pintype "bidirectional"))
    )
    (net (code "293") (name "/N$LEDR27") (class "Default")
      (node (ref "27") (pin "4") (pinfunction "RED_4") (pintype "bidirectional"))
      (node (ref "IC2") (pin "43") (pinfunction "OUTR13_43") (pintype "bidirectional"))
    )
    (net (code "294") (name "/N$LEDR28") (class "Default")
      (node (ref "28") (pin "4") (pinfunction "RED_4") (pintype "bidirectional"))
      (node (ref "IC2") (pin "46") (pinfunction "OUTR9_46") (pintype "bidirectional"))
    )
    (net (code "295") (name "/N$LEDR29") (class "Default")
      (node (ref "29") (pin "4") (pinfunction "RED_4") (pintype "bidirectional"))
      (node (ref "IC2") (pin "5") (pinfunction "OUTR4_5") (pintype "bidirectional"))
    )
    (net (code "296") (name "/N$LEDR30") (class "Default")
      (node (ref "30") (pin "4") (pinfunction "RED_4") (pintype "bidirectional"))
      (node (ref "IC2") (pin "8") (pinfunction "OUTR0_8") (pintype "bidirectional"))
    )
    (net (code "297") (name "/N$LEDR31") (class "Default")
      (node (ref "31") (pin "4") (pinfunction "RED_4") (pintype "bidirectional"))
      (node (ref "IC2") (pin "49") (pinfunction "OUTR12_49") (pintype "bidirectional"))
    )
    (net (code "298") (name "/N$LEDR32") (class "Default")
      (node (ref "32") (pin "4") (pinfunction "RED_4") (pintype "bidirectional"))
      (node (ref "IC2") (pin "52") (pinfunction "OUTR8_52") (pintype "bidirectional"))
    )
    (net (code "299") (name "/N$LEDR33") (class "Default")
      (node (ref "33") (pin "4") (pinfunction "RED_4") (pintype "bidirectional"))
      (node (ref "IC3") (pin "26") (pinfunction "OUTR7_26") (pintype "bidirectional"))
    )
    (net (code "300") (name "/N$LEDR34") (class "Default")
      (node (ref "34") (pin "4") (pinfunction "RED_4") (pintype "bidirectional"))
      (node (ref "IC3") (pin "23") (pinfunction "OUTR3_23") (pintype "bidirectional"))
    )
    (net (code "301") (name "/N$LEDR35") (class "Default")
      (node (ref "35") (pin "4") (pinfunction "RED_4") (pintype "bidirectional"))
      (node (ref "IC3") (pin "31") (pinfunction "OUTR11_31") (pintype "bidirectional"))
    )
    (net (code "302") (name "/N$LEDR36") (class "Default")
      (node (ref "36") (pin "4") (pinfunction "RED_4") (pintype "bidirectional"))
      (node (ref "IC3") (pin "34") (pinfunction "OUTR15_34") (pintype "bidirectional"))
    )
    (net (code "303") (name "/N$LEDR37") (class "Default")
      (node (ref "37") (pin "4") (pinfunction "RED_4") (pintype "bidirectional"))
      (node (ref "IC3") (pin "20") (pinfunction "OUTR6_20") (pintype "bidirectional"))
    )
    (net (code "304") (name "/N$LEDR38") (class "Default")
      (node (ref "38") (pin "4") (pinfunction "RED_4") (pintype "bidirectional"))
      (node (ref "IC3") (pin "17") (pinfunction "OUTR2_17") (pintype "bidirectional"))
    )
    (net (code "305") (name "/N$LEDR39") (class "Default")
      (node (ref "39") (pin "4") (pinfunction "RED_4") (pintype "bidirectional"))
      (node (ref "IC3") (pin "37") (pinfunction "OUTR10_37") (pintype "bidirectional"))
    )
    (net (code "306") (name "/N$LEDR40") (class "Default")
      (node (ref "40") (pin "4") (pinfunction "RED_4") (pintype "bidirectional"))
      (node (ref "IC3") (pin "40") (pinfunction "OUTR14_40") (pintype "bidirectional"))
    )
    (net (code "307") (name "/N$LEDR41") (class "Default")
      (node (ref "41") (pin "4") (pinfunction "RED_4") (pintype "bidirectional"))
      (node (ref "IC3") (pin "14") (pinfunction "OUTR1_14") (pintype "bidirectional"))
    )
    (net (code "308") (name "/N$LEDR42") (class "Default")
      (node (ref "42") (pin "4") (pinfunction "RED_4") (pintype "bidirectional"))
      (node (ref "IC3") (pin "11") (pinfunction "OUTR5_11") (pintype "bidirectional"))
    )
    (net (code "309") (name "/N$LEDR43") (class "Default")
      (node (ref "43") (pin "4") (pinfunction "RED_4") (pintype "bidirectional"))
      (node (ref "IC3") (pin "43") (pinfunction "OUTR13_43") (pintype "bidirectional"))
    )
    (net (code "310") (name "/N$LEDR44") (class "Default")
      (node (ref "44") (pin "4") (pinfunction "RED_4") (pintype "bidirectional"))
      (node (ref "IC3") (pin "46") (pinfunction "OUTR9_46") (pintype "bidirectional"))
    )
    (net (code "311") (name "/N$LEDR45") (class "Default")
      (node (ref "45") (pin "4") (pinfunction "RED_4") (pintype "bidirectional"))
      (node (ref "IC3") (pin "5") (pinfunction "OUTR4_5") (pintype "bidirectional"))
    )
    (net (code "312") (name "/N$LEDR46") (class "Default")
      (node (ref "46") (pin "4") (pinfunction "RED_4") (pintype "bidirectional"))
      (node (ref "IC3") (pin "8") (pinfunction "OUTR0_8") (pintype "bidirectional"))
    )
    (net (code "313") (name "/N$LEDR47") (class "Default")
      (node (ref "47") (pin "4") (pinfunction "RED_4") (pintype "bidirectional"))
      (node (ref "IC3") (pin "49") (pinfunction "OUTR12_49") (pintype "bidirectional"))
    )
    (net (code "314") (name "/N$LEDR48") (class "Default")
      (node (ref "48") (pin "4") (pinfunction "RED_4") (pintype "bidirectional"))
      (node (ref "IC3") (pin "52") (pinfunction "OUTR8_52") (pintype "bidirectional"))
    )
    (net (code "315") (name "/N$LEDR49") (class "Default")
      (node (ref "49") (pin "4") (pinfunction "RED_4") (pintype "bidirectional"))
      (node (ref "IC4") (pin "26") (pinfunction "OUTR7_26") (pintype "bidirectional"))
    )
    (net (code "316") (name "/N$LEDR50") (class "Default")
      (node (ref "50") (pin "4") (pinfunction "RED_4") (pintype "bidirectional"))
      (node (ref "IC4") (pin "23") (pinfunction "OUTR3_23") (pintype "bidirectional"))
    )
    (net (code "317") (name "/N$LEDR51") (class "Default")
      (node (ref "51") (pin "4") (pinfunction "RED_4") (pintype "bidirectional"))
      (node (ref "IC4") (pin "31") (pinfunction "OUTR11_31") (pintype "bidirectional"))
    )
    (net (code "318") (name "/N$LEDR52") (class "Default")
      (node (ref "52") (pin "4") (pinfunction "RED_4") (pintype "bidirectional"))
      (node (ref "IC4") (pin "34") (pinfunction "OUTR15_34") (pintype "bidirectional"))
    )
    (net (code "319") (name "/N$LEDR53") (class "Default")
      (node (ref "53") (pin "4") (pinfunction "RED_4") (pintype "bidirectional"))
      (node (ref "IC4") (pin "20") (pinfunction "OUTR6_20") (pintype "bidirectional"))
    )
    (net (code "320") (name "/N$LEDR54") (class "Default")
      (node (ref "54") (pin "4") (pinfunction "RED_4") (pintype "bidirectional"))
      (node (ref "IC4") (pin "17") (pinfunction "OUTR2_17") (pintype "bidirectional"))
    )
    (net (code "321") (name "/N$LEDR55") (class "Default")
      (node (ref "55") (pin "4") (pinfunction "RED_4") (pintype "bidirectional"))
      (node (ref "IC4") (pin "37") (pinfunction "OUTR10_37") (pintype "bidirectional"))
    )
    (net (code "322") (name "/N$LEDR56") (class "Default")
      (node (ref "56") (pin "4") (pinfunction "RED_4") (pintype "bidirectional"))
      (node (ref "IC4") (pin "40") (pinfunction "OUTR14_40") (pintype "bidirectional"))
    )
    (net (code "323") (name "/N$LEDR57") (class "Default")
      (node (ref "57") (pin "4") (pinfunction "RED_4") (pintype "bidirectional"))
      (node (ref "IC4") (pin "14") (pinfunction "OUTR1_14") (pintype "bidirectional"))
    )
    (net (code "324") (name "/N$LEDR58") (class "Default")
      (node (ref "58") (pin "4") (pinfunction "RED_4") (pintype "bidirectional"))
      (node (ref "IC4") (pin "11") (pinfunction "OUTR5_11") (pintype "bidirectional"))
    )
    (net (code "325") (name "/N$LEDR59") (class "Default")
      (node (ref "59") (pin "4") (pinfunction "RED_4") (pintype "bidirectional"))
      (node (ref "IC4") (pin "43") (pinfunction "OUTR13_43") (pintype "bidirectional"))
    )
    (net (code "326") (name "/N$LEDR60") (class "Default")
      (node (ref "60") (pin "4") (pinfunction "RED_4") (pintype "bidirectional"))
      (node (ref "IC4") (pin "46") (pinfunction "OUTR9_46") (pintype "bidirectional"))
    )
    (net (code "327") (name "/N$LEDR61") (class "Default")
      (node (ref "61") (pin "4") (pinfunction "RED_4") (pintype "bidirectional"))
      (node (ref "IC4") (pin "5") (pinfunction "OUTR4_5") (pintype "bidirectional"))
    )
    (net (code "328") (name "/N$LEDR62") (class "Default")
      (node (ref "62") (pin "4") (pinfunction "RED_4") (pintype "bidirectional"))
      (node (ref "IC4") (pin "8") (pinfunction "OUTR0_8") (pintype "bidirectional"))
    )
    (net (code "329") (name "/N$LEDR63") (class "Default")
      (node (ref "63") (pin "4") (pinfunction "RED_4") (pintype "bidirectional"))
      (node (ref "IC4") (pin "49") (pinfunction "OUTR12_49") (pintype "bidirectional"))
    )
    (net (code "330") (name "/N$LEDR64") (class "Default")
      (node (ref "64") (pin "4") (pinfunction "RED_4") (pintype "bidirectional"))
      (node (ref "IC4") (pin "52") (pinfunction "OUTR8_52") (pintype "bidirectional"))
    )
    (net (code "331") (name "/N$LEDR65") (class "Default")
      (node (ref "65") (pin "4") (pinfunction "RED_4") (pintype "bidirectional"))
      (node (ref "IC5") (pin "26") (pinfunction "OUTR7_26") (pintype "bidirectional"))
    )
    (net (code "332") (name "/N$LEDR66") (class "Default")
      (node (ref "66") (pin "4") (pinfunction "RED_4") (pintype "bidirectional"))
      (node (ref "IC5") (pin "23") (pinfunction "OUTR3_23") (pintype "bidirectional"))
    )
    (net (code "333") (name "/N$LEDR67") (class "Default")
      (node (ref "67") (pin "4") (pinfunction "RED_4") (pintype "bidirectional"))
      (node (ref "IC5") (pin "31") (pinfunction "OUTR11_31") (pintype "bidirectional"))
    )
    (net (code "334") (name "/N$LEDR68") (class "Default")
      (node (ref "68") (pin "4") (pinfunction "RED_4") (pintype "bidirectional"))
      (node (ref "IC5") (pin "34") (pinfunction "OUTR15_34") (pintype "bidirectional"))
    )
    (net (code "335") (name "/N$LEDR69") (class "Default")
      (node (ref "69") (pin "4") (pinfunction "RED_4") (pintype "bidirectional"))
      (node (ref "IC5") (pin "20") (pinfunction "OUTR6_20") (pintype "bidirectional"))
    )
    (net (code "336") (name "/N$LEDR70") (class "Default")
      (node (ref "70") (pin "4") (pinfunction "RED_4") (pintype "bidirectional"))
      (node (ref "IC5") (pin "17") (pinfunction "OUTR2_17") (pintype "bidirectional"))
    )
    (net (code "337") (name "/N$LEDR71") (class "Default")
      (node (ref "71") (pin "4") (pinfunction "RED_4") (pintype "bidirectional"))
      (node (ref "IC5") (pin "37") (pinfunction "OUTR10_37") (pintype "bidirectional"))
    )
    (net (code "338") (name "/N$LEDR72") (class "Default")
      (node (ref "72") (pin "4") (pinfunction "RED_4") (pintype "bidirectional"))
      (node (ref "IC5") (pin "40") (pinfunction "OUTR14_40") (pintype "bidirectional"))
    )
    (net (code "339") (name "/N$LEDR73") (class "Default")
      (node (ref "73") (pin "4") (pinfunction "RED_4") (pintype "bidirectional"))
      (node (ref "IC5") (pin "14") (pinfunction "OUTR1_14") (pintype "bidirectional"))
    )
    (net (code "340") (name "/N$LEDR74") (class "Default")
      (node (ref "74") (pin "4") (pinfunction "RED_4") (pintype "bidirectional"))
      (node (ref "IC5") (pin "11") (pinfunction "OUTR5_11") (pintype "bidirectional"))
    )
    (net (code "341") (name "/N$LEDR75") (class "Default")
      (node (ref "75") (pin "4") (pinfunction "RED_4") (pintype "bidirectional"))
      (node (ref "IC5") (pin "43") (pinfunction "OUTR13_43") (pintype "bidirectional"))
    )
    (net (code "342") (name "/N$LEDR76") (class "Default")
      (node (ref "76") (pin "4") (pinfunction "RED_4") (pintype "bidirectional"))
      (node (ref "IC5") (pin "46") (pinfunction "OUTR9_46") (pintype "bidirectional"))
    )
    (net (code "343") (name "/N$LEDR77") (class "Default")
      (node (ref "77") (pin "4") (pinfunction "RED_4") (pintype "bidirectional"))
      (node (ref "IC5") (pin "5") (pinfunction "OUTR4_5") (pintype "bidirectional"))
    )
    (net (code "344") (name "/N$LEDR78") (class "Default")
      (node (ref "78") (pin "4") (pinfunction "RED_4") (pintype "bidirectional"))
      (node (ref "IC5") (pin "8") (pinfunction "OUTR0_8") (pintype "bidirectional"))
    )
    (net (code "345") (name "/N$LEDR79") (class "Default")
      (node (ref "79") (pin "4") (pinfunction "RED_4") (pintype "bidirectional"))
      (node (ref "IC5") (pin "49") (pinfunction "OUTR12_49") (pintype "bidirectional"))
    )
    (net (code "346") (name "/N$LEDR80") (class "Default")
      (node (ref "80") (pin "4") (pinfunction "RED_4") (pintype "bidirectional"))
      (node (ref "IC5") (pin "52") (pinfunction "OUTR8_52") (pintype "bidirectional"))
    )
    (net (code "347") (name "/N$LEDR81") (class "Default")
      (node (ref "81") (pin "4") (pinfunction "RED_4") (pintype "bidirectional"))
      (node (ref "IC6") (pin "26") (pinfunction "OUTR7_26") (pintype "bidirectional"))
    )
    (net (code "348") (name "/N$LEDR82") (class "Default")
      (node (ref "82") (pin "4") (pinfunction "RED_4") (pintype "bidirectional"))
      (node (ref "IC6") (pin "23") (pinfunction "OUTR3_23") (pintype "bidirectional"))
    )
    (net (code "349") (name "/N$LEDR83") (class "Default")
      (node (ref "83") (pin "4") (pinfunction "RED_4") (pintype "bidirectional"))
      (node (ref "IC6") (pin "31") (pinfunction "OUTR11_31") (pintype "bidirectional"))
    )
    (net (code "350") (name "/N$LEDR84") (class "Default")
      (node (ref "84") (pin "4") (pinfunction "RED_4") (pintype "bidirectional"))
      (node (ref "IC6") (pin "34") (pinfunction "OUTR15_34") (pintype "bidirectional"))
    )
    (net (code "351") (name "/N$LEDR85") (class "Default")
      (node (ref "85") (pin "4") (pinfunction "RED_4") (pintype "bidirectional"))
      (node (ref "IC6") (pin "20") (pinfunction "OUTR6_20") (pintype "bidirectional"))
    )
    (net (code "352") (name "/N$LEDR86") (class "Default")
      (node (ref "86") (pin "4") (pinfunction "RED_4") (pintype "bidirectional"))
      (node (ref "IC6") (pin "17") (pinfunction "OUTR2_17") (pintype "bidirectional"))
    )
    (net (code "353") (name "/N$LEDR87") (class "Default")
      (node (ref "87") (pin "4") (pinfunction "RED_4") (pintype "bidirectional"))
      (node (ref "IC6") (pin "37") (pinfunction "OUTR10_37") (pintype "bidirectional"))
    )
    (net (code "354") (name "/N$LEDR88") (class "Default")
      (node (ref "88") (pin "4") (pinfunction "RED_4") (pintype "bidirectional"))
      (node (ref "IC6") (pin "40") (pinfunction "OUTR14_40") (pintype "bidirectional"))
    )
    (net (code "355") (name "/N$LEDR89") (class "Default")
      (node (ref "89") (pin "4") (pinfunction "RED_4") (pintype "bidirectional"))
      (node (ref "IC6") (pin "14") (pinfunction "OUTR1_14") (pintype "bidirectional"))
    )
    (net (code "356") (name "/N$LEDR90") (class "Default")
      (node (ref "90") (pin "4") (pinfunction "RED_4") (pintype "bidirectional"))
      (node (ref "IC6") (pin "11") (pinfunction "OUTR5_11") (pintype "bidirectional"))
    )
    (net (code "357") (name "/N$LEDR91") (class "Default")
      (node (ref "91") (pin "4") (pinfunction "RED_4") (pintype "bidirectional"))
      (node (ref "IC6") (pin "43") (pinfunction "OUTR13_43") (pintype "bidirectional"))
    )
    (net (code "358") (name "/N$LEDR92") (class "Default")
      (node (ref "92") (pin "4") (pinfunction "RED_4") (pintype "bidirectional"))
      (node (ref "IC6") (pin "46") (pinfunction "OUTR9_46") (pintype "bidirectional"))
    )
    (net (code "359") (name "/N$LEDR93") (class "Default")
      (node (ref "93") (pin "4") (pinfunction "RED_4") (pintype "bidirectional"))
      (node (ref "IC6") (pin "5") (pinfunction "OUTR4_5") (pintype "bidirectional"))
    )
    (net (code "360") (name "/N$LEDR94") (class "Default")
      (node (ref "94") (pin "4") (pinfunction "RED_4") (pintype "bidirectional"))
      (node (ref "IC6") (pin "8") (pinfunction "OUTR0_8") (pintype "bidirectional"))
    )
    (net (code "361") (name "/N$LEDR95") (class "Default")
      (node (ref "95") (pin "4") (pinfunction "RED_4") (pintype "bidirectional"))
      (node (ref "IC6") (pin "49") (pinfunction "OUTR12_49") (pintype "bidirectional"))
    )
    (net (code "362") (name "/N$LEDR96") (class "Default")
      (node (ref "96") (pin "4") (pinfunction "RED_4") (pintype "bidirectional"))
      (node (ref "IC6") (pin "52") (pinfunction "OUTR8_52") (pintype "bidirectional"))
    )
    (net (code "363") (name "/N$LEDR97") (class "Default")
      (node (ref "97") (pin "4") (pinfunction "RED_4") (pintype "bidirectional"))
      (node (ref "IC7") (pin "26") (pinfunction "OUTR7_26") (pintype "bidirectional"))
    )
    (net (code "364") (name "/N$LEDR98") (class "Default")
      (node (ref "98") (pin "4") (pinfunction "RED_4") (pintype "bidirectional"))
      (node (ref "IC7") (pin "23") (pinfunction "OUTR3_23") (pintype "bidirectional"))
    )
    (net (code "365") (name "/N$LEDR99") (class "Default")
      (node (ref "99") (pin "4") (pinfunction "RED_4") (pintype "bidirectional"))
      (node (ref "IC7") (pin "31") (pinfunction "OUTR11_31") (pintype "bidirectional"))
    )
    (net (code "366") (name "/N$LEDR100") (class "Default")
      (node (ref "100") (pin "4") (pinfunction "RED_4") (pintype "bidirectional"))
      (node (ref "IC7") (pin "34") (pinfunction "OUTR15_34") (pintype "bidirectional"))
    )
    (net (code "367") (name "/N$LEDR101") (class "Default")
      (node (ref "101") (pin "4") (pinfunction "RED_4") (pintype "bidirectional"))
      (node (ref "IC7") (pin "20") (pinfunction "OUTR6_20") (pintype "bidirectional"))
    )
    (net (code "368") (name "/N$LEDR102") (class "Default")
      (node (ref "102") (pin "4") (pinfunction "RED_4") (pintype "bidirectional"))
      (node (ref "IC7") (pin "17") (pinfunction "OUTR2_17") (pintype "bidirectional"))
    )
    (net (code "369") (name "/N$LEDR103") (class "Default")
      (node (ref "103") (pin "4") (pinfunction "RED_4") (pintype "bidirectional"))
      (node (ref "IC7") (pin "37") (pinfunction "OUTR10_37") (pintype "bidirectional"))
    )
    (net (code "370") (name "/N$LEDR104") (class "Default")
      (node (ref "104") (pin "4") (pinfunction "RED_4") (pintype "bidirectional"))
      (node (ref "IC7") (pin "40") (pinfunction "OUTR14_40") (pintype "bidirectional"))
    )
    (net (code "371") (name "/N$LEDR105") (class "Default")
      (node (ref "105") (pin "4") (pinfunction "RED_4") (pintype "bidirectional"))
      (node (ref "IC7") (pin "14") (pinfunction "OUTR1_14") (pintype "bidirectional"))
    )
    (net (code "372") (name "/N$LEDR106") (class "Default")
      (node (ref "106") (pin "4") (pinfunction "RED_4") (pintype "bidirectional"))
      (node (ref "IC7") (pin "11") (pinfunction "OUTR5_11") (pintype "bidirectional"))
    )
    (net (code "373") (name "/N$LEDR107") (class "Default")
      (node (ref "107") (pin "4") (pinfunction "RED_4") (pintype "bidirectional"))
      (node (ref "IC7") (pin "43") (pinfunction "OUTR13_43") (pintype "bidirectional"))
    )
    (net (code "374") (name "/N$LEDR108") (class "Default")
      (node (ref "108") (pin "4") (pinfunction "RED_4") (pintype "bidirectional"))
      (node (ref "IC7") (pin "46") (pinfunction "OUTR9_46") (pintype "bidirectional"))
    )
    (net (code "375") (name "/N$LEDR109") (class "Default")
      (node (ref "109") (pin "4") (pinfunction "RED_4") (pintype "bidirectional"))
      (node (ref "IC7") (pin "5") (pinfunction "OUTR4_5") (pintype "bidirectional"))
    )
    (net (code "376") (name "/N$LEDR110") (class "Default")
      (node (ref "110") (pin "4") (pinfunction "RED_4") (pintype "bidirectional"))
      (node (ref "IC7") (pin "8") (pinfunction "OUTR0_8") (pintype "bidirectional"))
    )
    (net (code "377") (name "/N$LEDR111") (class "Default")
      (node (ref "111") (pin "4") (pinfunction "RED_4") (pintype "bidirectional"))
      (node (ref "IC7") (pin "49") (pinfunction "OUTR12_49") (pintype "bidirectional"))
    )
    (net (code "378") (name "/N$LEDR112") (class "Default")
      (node (ref "112") (pin "4") (pinfunction "RED_4") (pintype "bidirectional"))
      (node (ref "IC7") (pin "52") (pinfunction "OUTR8_52") (pintype "bidirectional"))
    )
    (net (code "379") (name "/N$LEDR113") (class "Default")
      (node (ref "113") (pin "4") (pinfunction "RED_4") (pintype "bidirectional"))
      (node (ref "IC8") (pin "26") (pinfunction "OUTR7_26") (pintype "bidirectional"))
    )
    (net (code "380") (name "/N$LEDR114") (class "Default")
      (node (ref "114") (pin "4") (pinfunction "RED_4") (pintype "bidirectional"))
      (node (ref "IC8") (pin "23") (pinfunction "OUTR3_23") (pintype "bidirectional"))
    )
    (net (code "381") (name "/N$LEDR115") (class "Default")
      (node (ref "115") (pin "4") (pinfunction "RED_4") (pintype "bidirectional"))
      (node (ref "IC8") (pin "31") (pinfunction "OUTR11_31") (pintype "bidirectional"))
    )
    (net (code "382") (name "/N$LEDR116") (class "Default")
      (node (ref "116") (pin "4") (pinfunction "RED_4") (pintype "bidirectional"))
      (node (ref "IC8") (pin "34") (pinfunction "OUTR15_34") (pintype "bidirectional"))
    )
    (net (code "383") (name "/N$LEDR117") (class "Default")
      (node (ref "117") (pin "4") (pinfunction "RED_4") (pintype "bidirectional"))
      (node (ref "IC8") (pin "20") (pinfunction "OUTR6_20") (pintype "bidirectional"))
    )
    (net (code "384") (name "/N$LEDR118") (class "Default")
      (node (ref "118") (pin "4") (pinfunction "RED_4") (pintype "bidirectional"))
      (node (ref "IC8") (pin "17") (pinfunction "OUTR2_17") (pintype "bidirectional"))
    )
    (net (code "385") (name "/N$LEDR119") (class "Default")
      (node (ref "119") (pin "4") (pinfunction "RED_4") (pintype "bidirectional"))
      (node (ref "IC8") (pin "37") (pinfunction "OUTR10_37") (pintype "bidirectional"))
    )
    (net (code "386") (name "/N$LEDR120") (class "Default")
      (node (ref "120") (pin "4") (pinfunction "RED_4") (pintype "bidirectional"))
      (node (ref "IC8") (pin "40") (pinfunction "OUTR14_40") (pintype "bidirectional"))
    )
    (net (code "387") (name "/SIN_1,2") (class "Default")
      (node (ref "IC2") (pin "1") (pinfunction "SIN_1") (pintype "bidirectional"))
      (node (ref "SV1") (pin "12") (pinfunction "12_12") (pintype "passive"))
    )
    (net (code "388") (name "/SIN_3,4") (class "Default")
      (node (ref "IC4") (pin "1") (pinfunction "SIN_1") (pintype "bidirectional"))
      (node (ref "SV1") (pin "11") (pinfunction "11_11") (pintype "passive"))
    )
    (net (code "389") (name "/SIN_5,6") (class "Default")
      (node (ref "IC6") (pin "1") (pinfunction "SIN_1") (pintype "bidirectional"))
      (node (ref "SV1") (pin "10") (pinfunction "10_10") (pintype "passive"))
    )
    (net (code "390") (name "/SIN_7,8") (class "Default")
      (node (ref "IC8") (pin "1") (pinfunction "SIN_1") (pintype "bidirectional"))
      (node (ref "SV1") (pin "9") (pinfunction "9_9") (pintype "passive"))
    )
    (net (code "391") (name "/SOUT1") (class "Default")
      (node (ref "IC1") (pin "28") (pinfunction "SOUT_28") (pintype "bidirectional"))
    )
    (net (code "392") (name "/SOUT2") (class "Default")
      (node (ref "IC1") (pin "1") (pinfunction "SIN_1") (pintype "bidirectional"))
      (node (ref "IC2") (pin "28") (pinfunction "SOUT_28") (pintype "bidirectional"))
    )
    (net (code "393") (name "/SOUT3") (class "Default")
      (node (ref "IC3") (pin "28") (pinfunction "SOUT_28") (pintype "bidirectional"))
    )
    (net (code "394") (name "/SOUT4") (class "Default")
      (node (ref "IC3") (pin "1") (pinfunction "SIN_1") (pintype "bidirectional"))
      (node (ref "IC4") (pin "28") (pinfunction "SOUT_28") (pintype "bidirectional"))
    )
    (net (code "395") (name "/SOUT5") (class "Default")
      (node (ref "IC5") (pin "28") (pinfunction "SOUT_28") (pintype "bidirectional"))
    )
    (net (code "396") (name "/SOUT6") (class "Default")
      (node (ref "IC5") (pin "1") (pinfunction "SIN_1") (pintype "bidirectional"))
      (node (ref "IC6") (pin "28") (pinfunction "SOUT_28") (pintype "bidirectional"))
    )
    (net (code "397") (name "/SOUT7") (class "Default")
      (node (ref "IC7") (pin "28") (pinfunction "SOUT_28") (pintype "bidirectional"))
    )
    (net (code "398") (name "/SOUT8") (class "Default")
      (node (ref "IC7") (pin "1") (pinfunction "SIN_1") (pintype "bidirectional"))
      (node (ref "IC8") (pin "28") (pinfunction "SOUT_28") (pintype "bidirectional"))
    )
    (net (code "399") (name "3V3_LOGIC") (class "Default")
      (node (ref "C1") (pin "1") (pinfunction "1_1") (pintype "passive"))
      (node (ref "C1B") (pin "1") (pinfunction "1_1") (pintype "passive"))
      (node (ref "C2") (pin "1") (pinfunction "1_1") (pintype "passive"))
      (node (ref "C28") (pin "1") (pinfunction "1_1") (pintype "passive"))
      (node (ref "C29") (pin "1") (pinfunction "1_1") (pintype "passive"))
      (node (ref "C2B") (pin "1") (pinfunction "1_1") (pintype "passive"))
      (node (ref "C3") (pin "1") (pinfunction "1_1") (pintype "passive"))
      (node (ref "C30") (pin "1") (pinfunction "1_1") (pintype "passive"))
      (node (ref "C31") (pin "1") (pinfunction "1_1") (pintype "passive"))
      (node (ref "C32") (pin "1") (pinfunction "1_1") (pintype "passive"))
      (node (ref "C33") (pin "1") (pinfunction "1_1") (pintype "passive"))
      (node (ref "C3B") (pin "1") (pinfunction "1_1") (pintype "passive"))
      (node (ref "C4") (pin "1") (pinfunction "1_1") (pintype "passive"))
      (node (ref "C4B") (pin "1") (pinfunction "1_1") (pintype "passive"))
      (node (ref "C5") (pin "1") (pinfunction "1_1") (pintype "passive"))
      (node (ref "C5B") (pin "1") (pinfunction "1_1") (pintype "passive"))
      (node (ref "C6") (pin "1") (pinfunction "1_1") (pintype "passive"))
      (node (ref "C6B") (pin "1") (pinfunction "1_1") (pintype "passive"))
      (node (ref "C7") (pin "1") (pinfunction "1_1") (pintype "passive"))
      (node (ref "C7B") (pin "1") (pinfunction "1_1") (pintype "passive"))
      (node (ref "C8") (pin "1") (pinfunction "1_1") (pintype "passive"))
      (node (ref "C8B") (pin "1") (pinfunction "1_1") (pintype "passive"))
      (node (ref "IC1") (pin "54") (pinfunction "VCC_54") (pintype "bidirectional"))
      (node (ref "IC10") (pin "5") (pinfunction "VCC_5") (pintype "bidirectional"))
      (node (ref "IC11") (pin "5") (pinfunction "VCC_5") (pintype "bidirectional"))
      (node (ref "IC2") (pin "54") (pinfunction "VCC_54") (pintype "bidirectional"))
      (node (ref "IC3") (pin "54") (pinfunction "VCC_54") (pintype "bidirectional"))
      (node (ref "IC4") (pin "54") (pinfunction "VCC_54") (pintype "bidirectional"))
      (node (ref "IC5") (pin "54") (pinfunction "VCC_54") (pintype "bidirectional"))
      (node (ref "IC6") (pin "54") (pinfunction "VCC_54") (pintype "bidirectional"))
      (node (ref "IC7") (pin "54") (pinfunction "VCC_54") (pintype "bidirectional"))
      (node (ref "IC8") (pin "54") (pinfunction "VCC_54") (pintype "bidirectional"))
      (node (ref "IC9") (pin "5") (pinfunction "VCC_5") (pintype "bidirectional"))
      (node (ref "SV1") (pin "1") (pinfunction "1_1") (pintype "passive"))
    )
    (net (code "400") (name "GSCLK") (class "Default")
      (node (ref "IC1") (pin "55") (pinfunction "GSCLK_55") (pintype "bidirectional"))
      (node (ref "IC11") (pin "4") (pinfunction "Y_4") (pintype "bidirectional"))
      (node (ref "IC2") (pin "55") (pinfunction "GSCLK_55") (pintype "bidirectional"))
      (node (ref "IC3") (pin "55") (pinfunction "GSCLK_55") (pintype "bidirectional"))
      (node (ref "IC4") (pin "55") (pinfunction "GSCLK_55") (pintype "bidirectional"))
      (node (ref "IC5") (pin "55") (pinfunction "GSCLK_55") (pintype "bidirectional"))
      (node (ref "IC6") (pin "55") (pinfunction "GSCLK_55") (pintype "bidirectional"))
      (node (ref "IC7") (pin "55") (pinfunction "GSCLK_55") (pintype "bidirectional"))
      (node (ref "IC8") (pin "55") (pinfunction "GSCLK_55") (pintype "bidirectional"))
    )
    (net (code "401") (name "GSCLK_FPGA") (class "Default")
      (node (ref "IC11") (pin "2") (pinfunction "A_2") (pintype "bidirectional"))
      (node (ref "SV1") (pin "3") (pinfunction "3_3") (pintype "passive"))
    )
    (net (code "402") (name "LAT") (class "Default")
      (node (ref "IC1") (pin "3") (pinfunction "LAT_3") (pintype "bidirectional"))
      (node (ref "IC2") (pin "3") (pinfunction "LAT_3") (pintype "bidirectional"))
      (node (ref "IC3") (pin "3") (pinfunction "LAT_3") (pintype "bidirectional"))
      (node (ref "IC4") (pin "3") (pinfunction "LAT_3") (pintype "bidirectional"))
      (node (ref "IC5") (pin "3") (pinfunction "LAT_3") (pintype "bidirectional"))
      (node (ref "IC6") (pin "3") (pinfunction "LAT_3") (pintype "bidirectional"))
      (node (ref "IC7") (pin "3") (pinfunction "LAT_3") (pintype "bidirectional"))
      (node (ref "IC8") (pin "3") (pinfunction "LAT_3") (pintype "bidirectional"))
      (node (ref "IC9") (pin "4") (pinfunction "Y_4") (pintype "bidirectional"))
    )
    (net (code "403") (name "LAT_FPGA") (class "Default")
      (node (ref "IC9") (pin "2") (pinfunction "A_2") (pintype "bidirectional"))
      (node (ref "SV1") (pin "5") (pinfunction "5_5") (pintype "passive"))
    )
    (net (code "404") (name "SCLK") (class "Default")
      (node (ref "IC1") (pin "2") (pinfunction "SCLK_2") (pintype "bidirectional"))
      (node (ref "IC10") (pin "4") (pinfunction "Y_4") (pintype "bidirectional"))
      (node (ref "IC2") (pin "2") (pinfunction "SCLK_2") (pintype "bidirectional"))
      (node (ref "IC3") (pin "2") (pinfunction "SCLK_2") (pintype "bidirectional"))
      (node (ref "IC4") (pin "2") (pinfunction "SCLK_2") (pintype "bidirectional"))
      (node (ref "IC5") (pin "2") (pinfunction "SCLK_2") (pintype "bidirectional"))
      (node (ref "IC6") (pin "2") (pinfunction "SCLK_2") (pintype "bidirectional"))
      (node (ref "IC7") (pin "2") (pinfunction "SCLK_2") (pintype "bidirectional"))
      (node (ref "IC8") (pin "2") (pinfunction "SCLK_2") (pintype "bidirectional"))
    )
    (net (code "405") (name "SCLK_FPGA") (class "Default")
      (node (ref "IC10") (pin "2") (pinfunction "A_2") (pintype "bidirectional"))
      (node (ref "SV1") (pin "7") (pinfunction "7_7") (pintype "passive"))
    )
    (net (code "406") (name "unconnected-(IC9-N.C.-Pad1)") (class "Default")
      (node (ref "IC9") (pin "1") (pinfunction "N.C._1") (pintype "no_connect"))
    )
    (net (code "407") (name "unconnected-(IC10-N.C.-Pad1)") (class "Default")
      (node (ref "IC10") (pin "1") (pinfunction "N.C._1") (pintype "no_connect"))
    )
    (net (code "408") (name "unconnected-(IC11-N.C.-Pad1)") (class "Default")
      (node (ref "IC11") (pin "1") (pinfunction "N.C._1") (pintype "no_connect"))
    )
  )
)
